# alan2.net
KiCad netlist of a schematic drawn in EAGLE
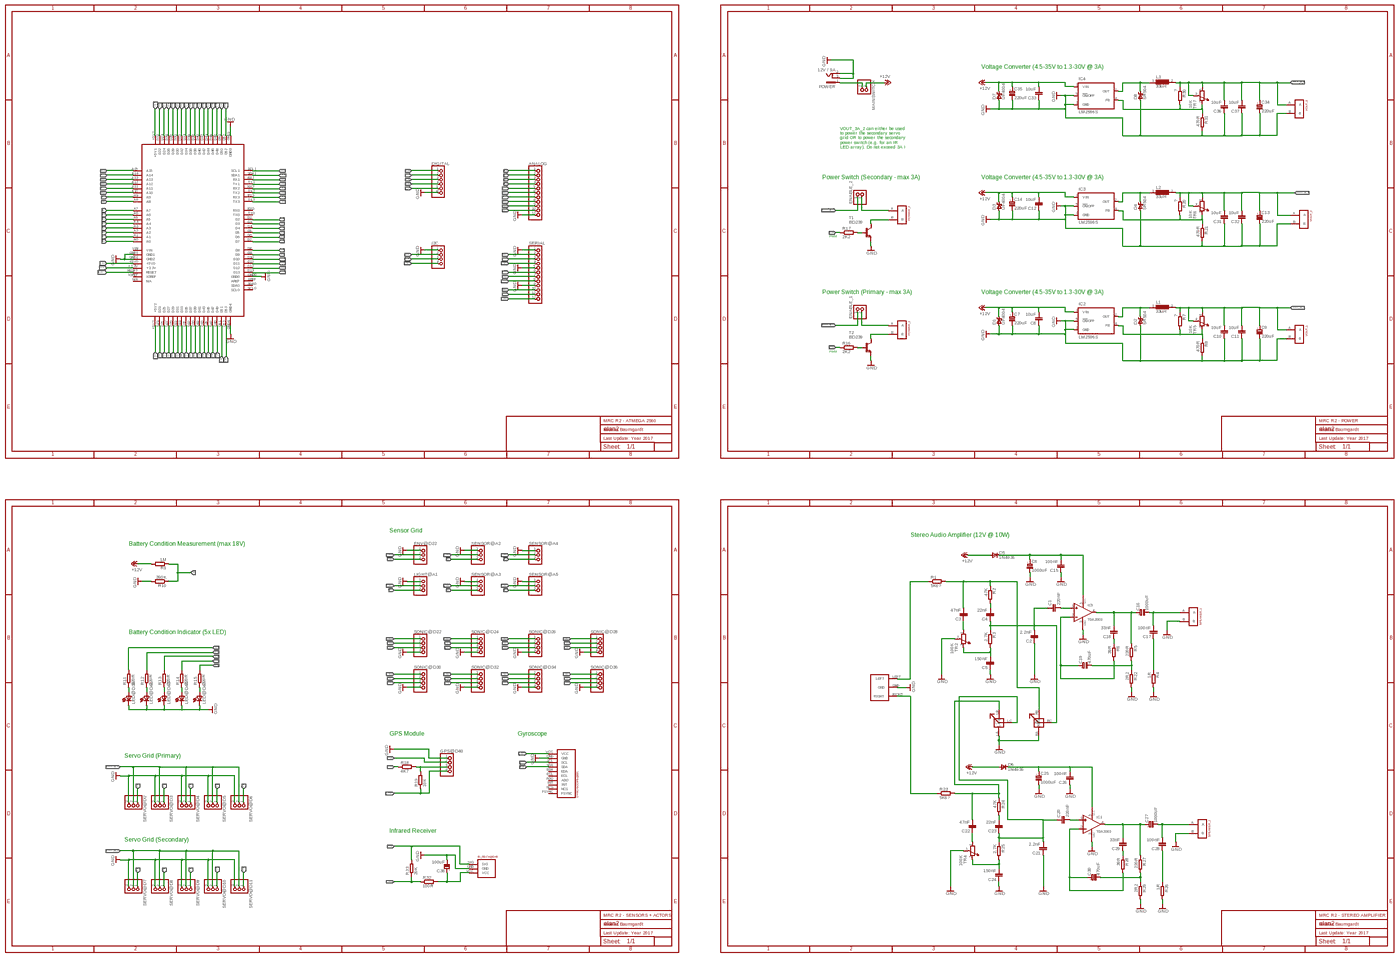
[diagram p0: schematic, sheet 1, overview]
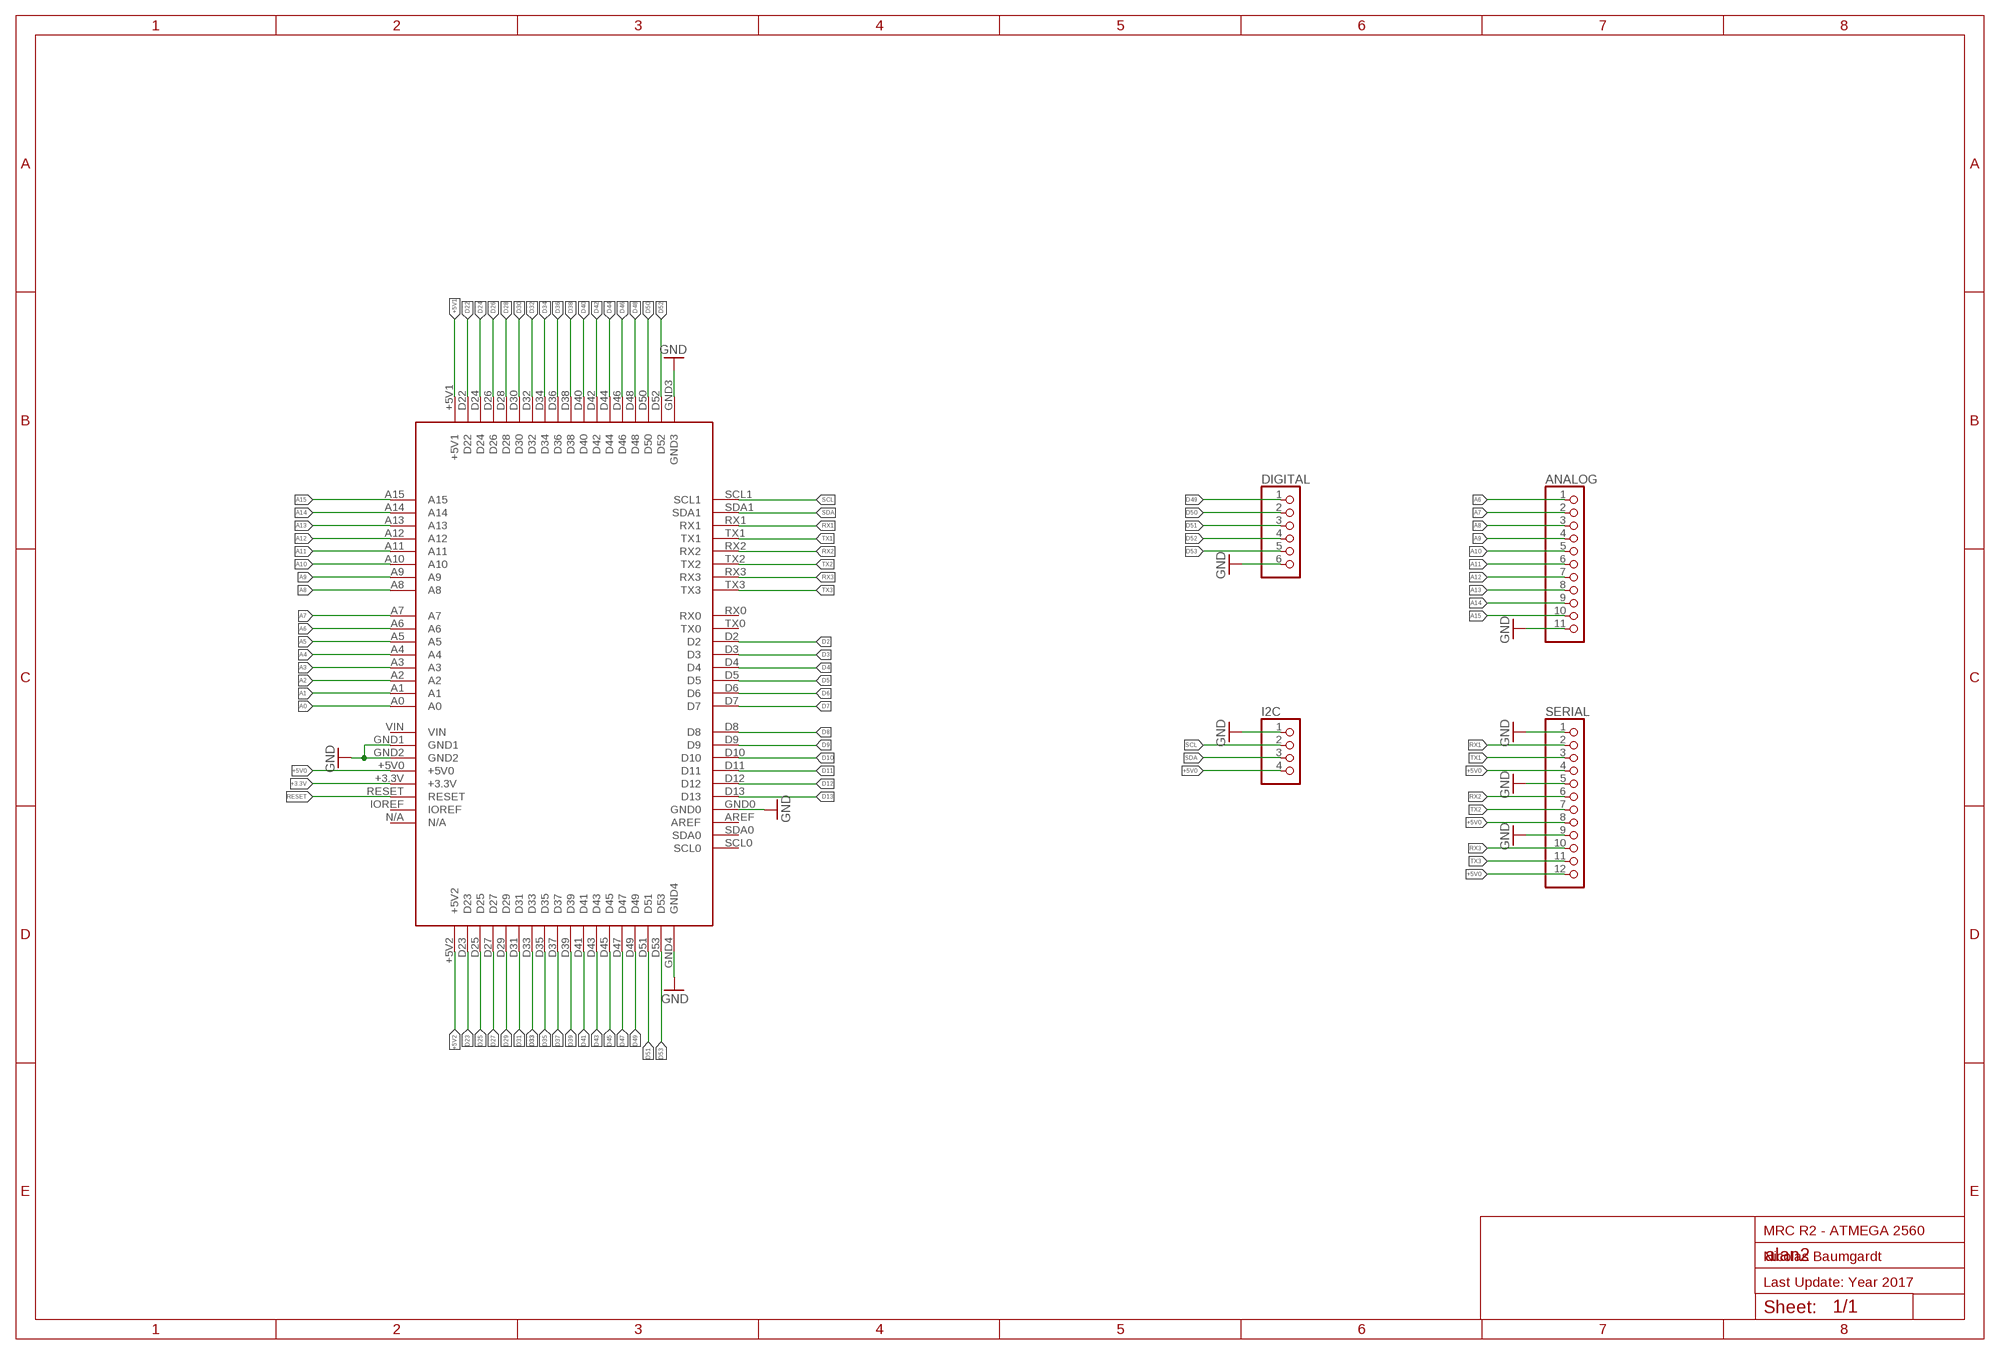
[diagram p1: schematic, sheet 1, part 1 of 4]
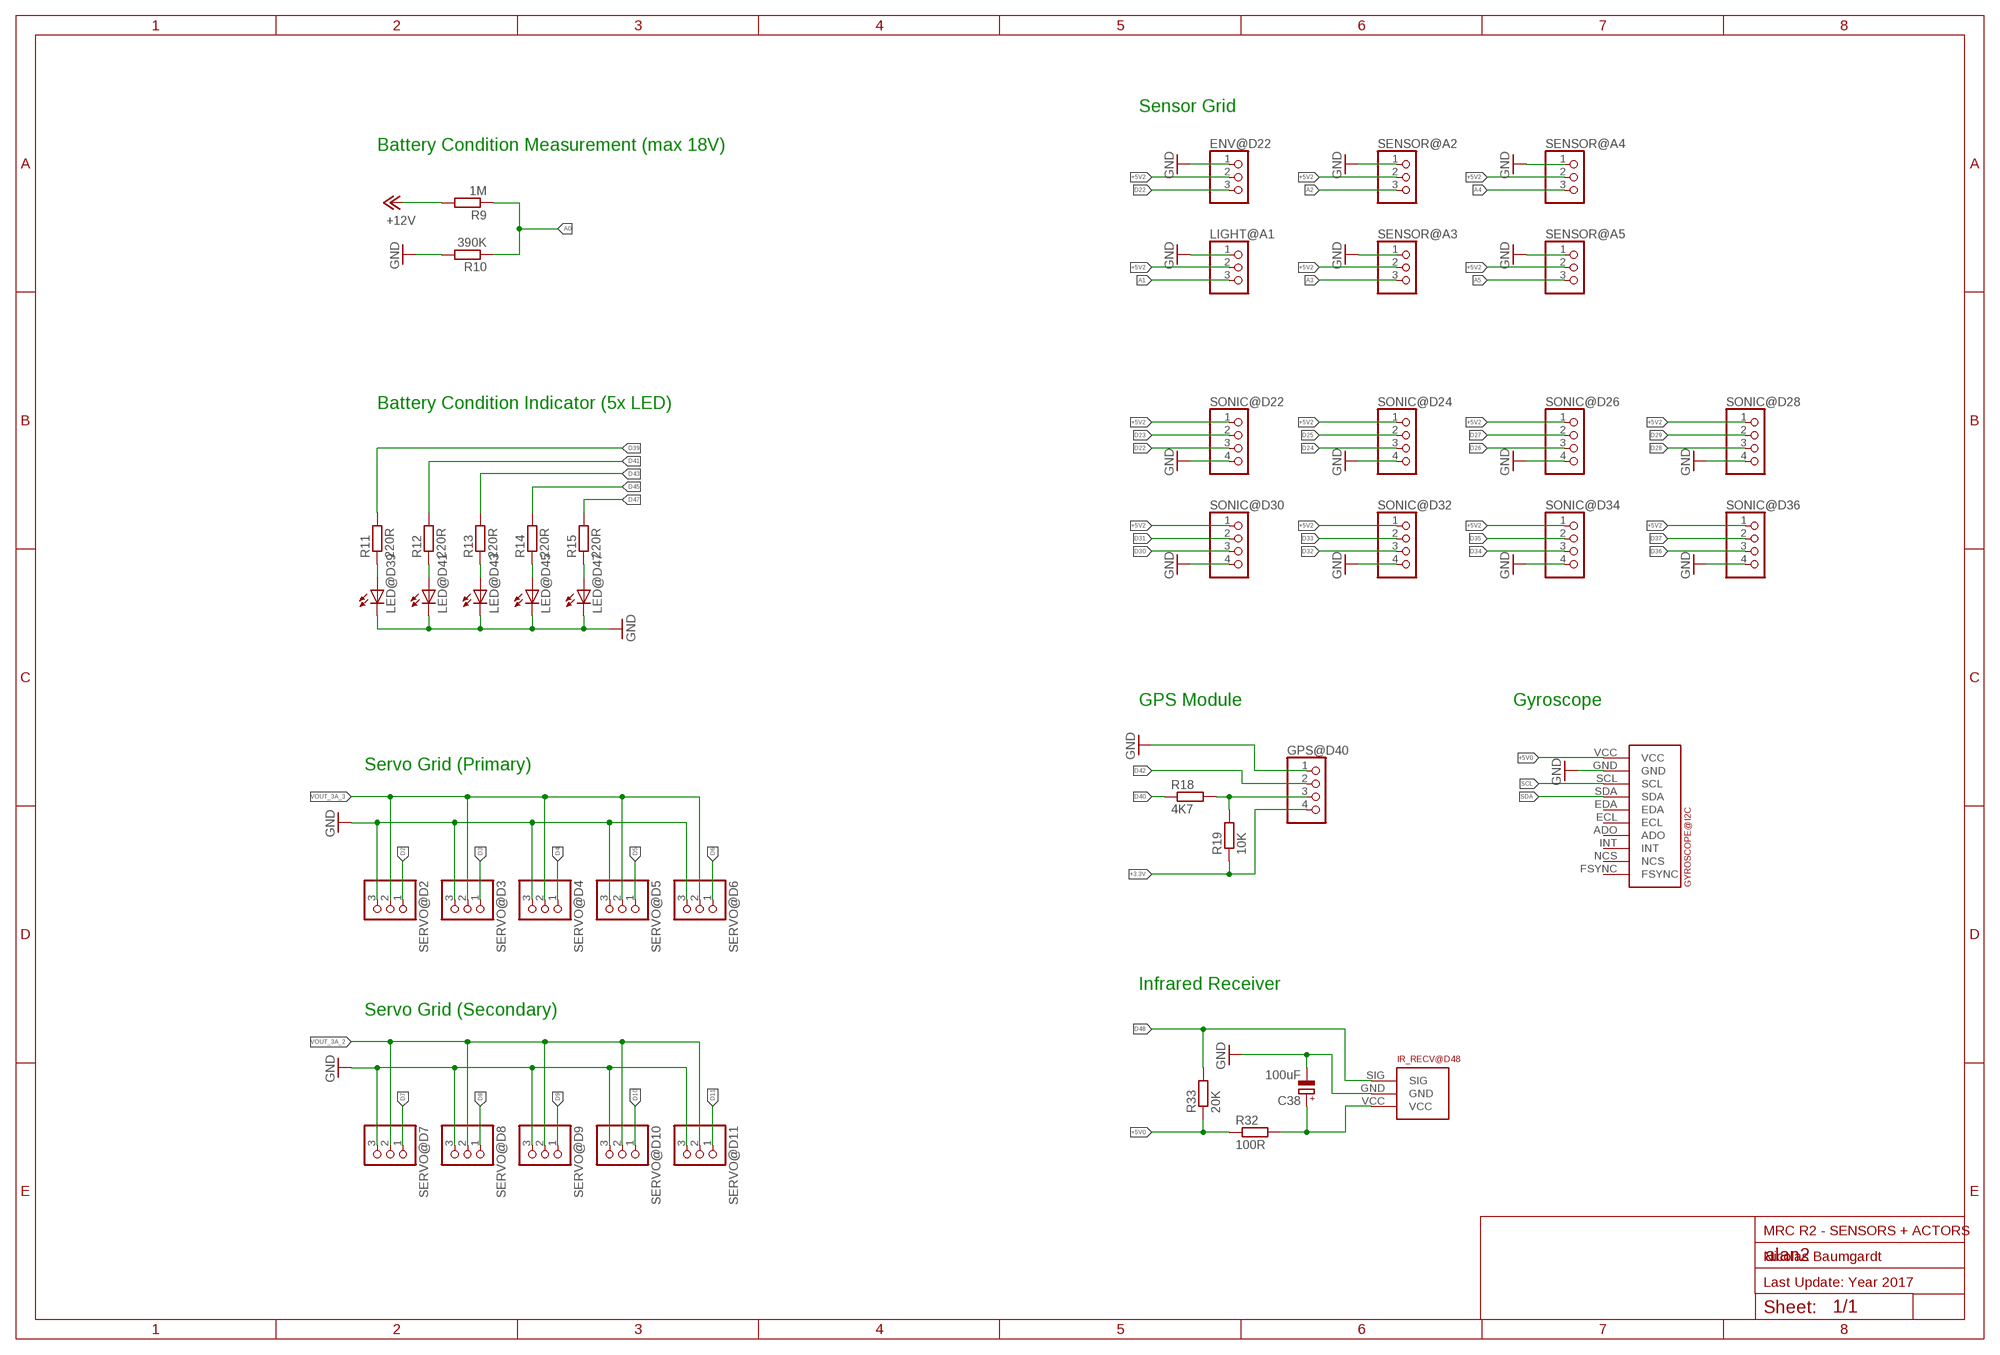
[diagram p2: schematic, sheet 1, part 2 of 4]
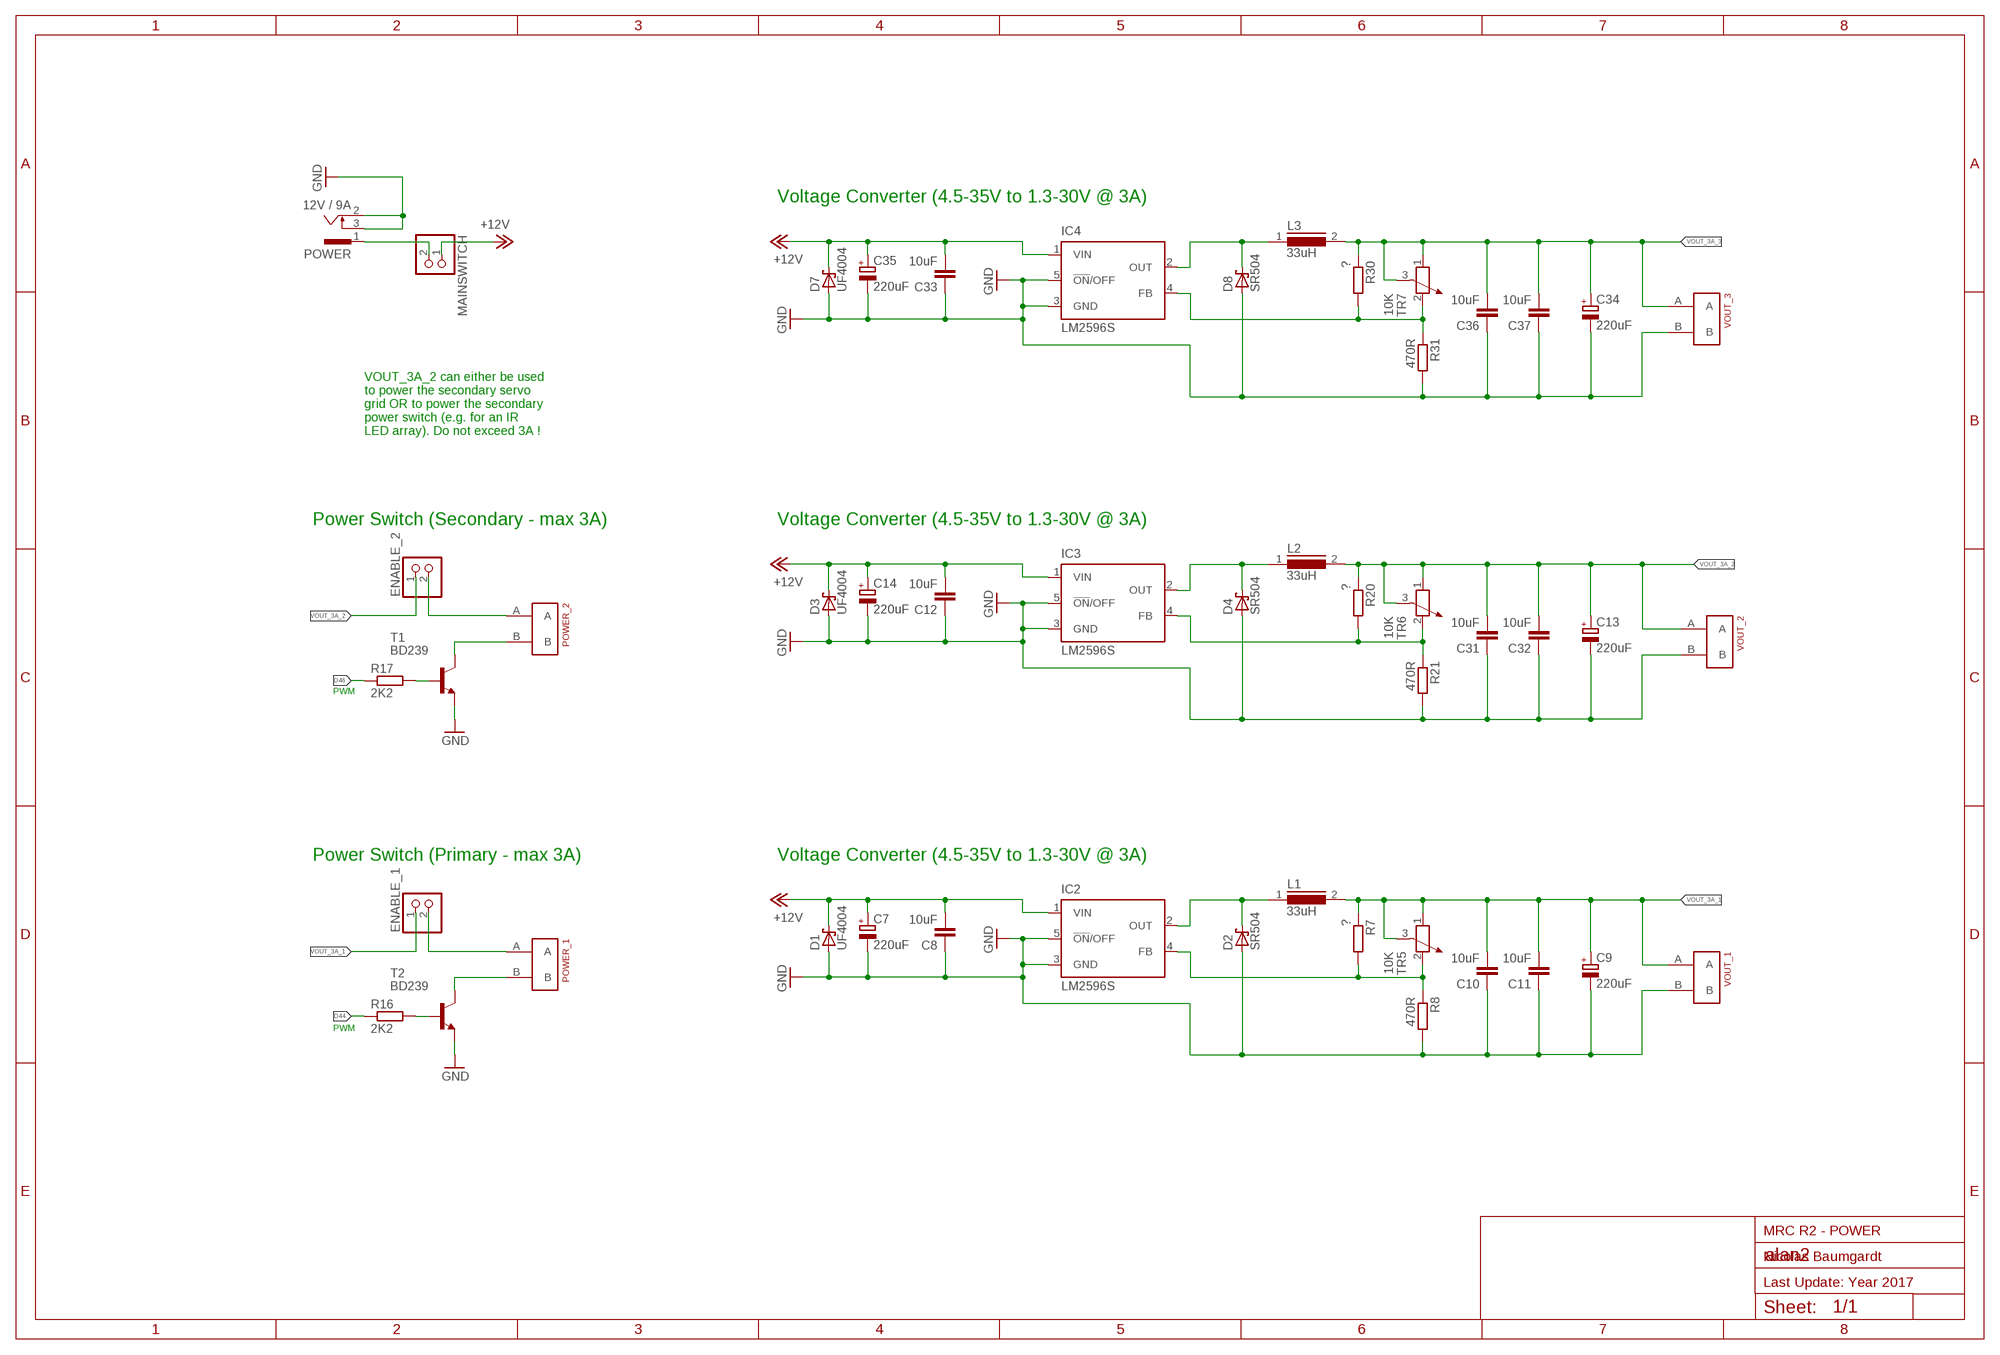
[diagram p3: schematic, sheet 1, part 3 of 4]
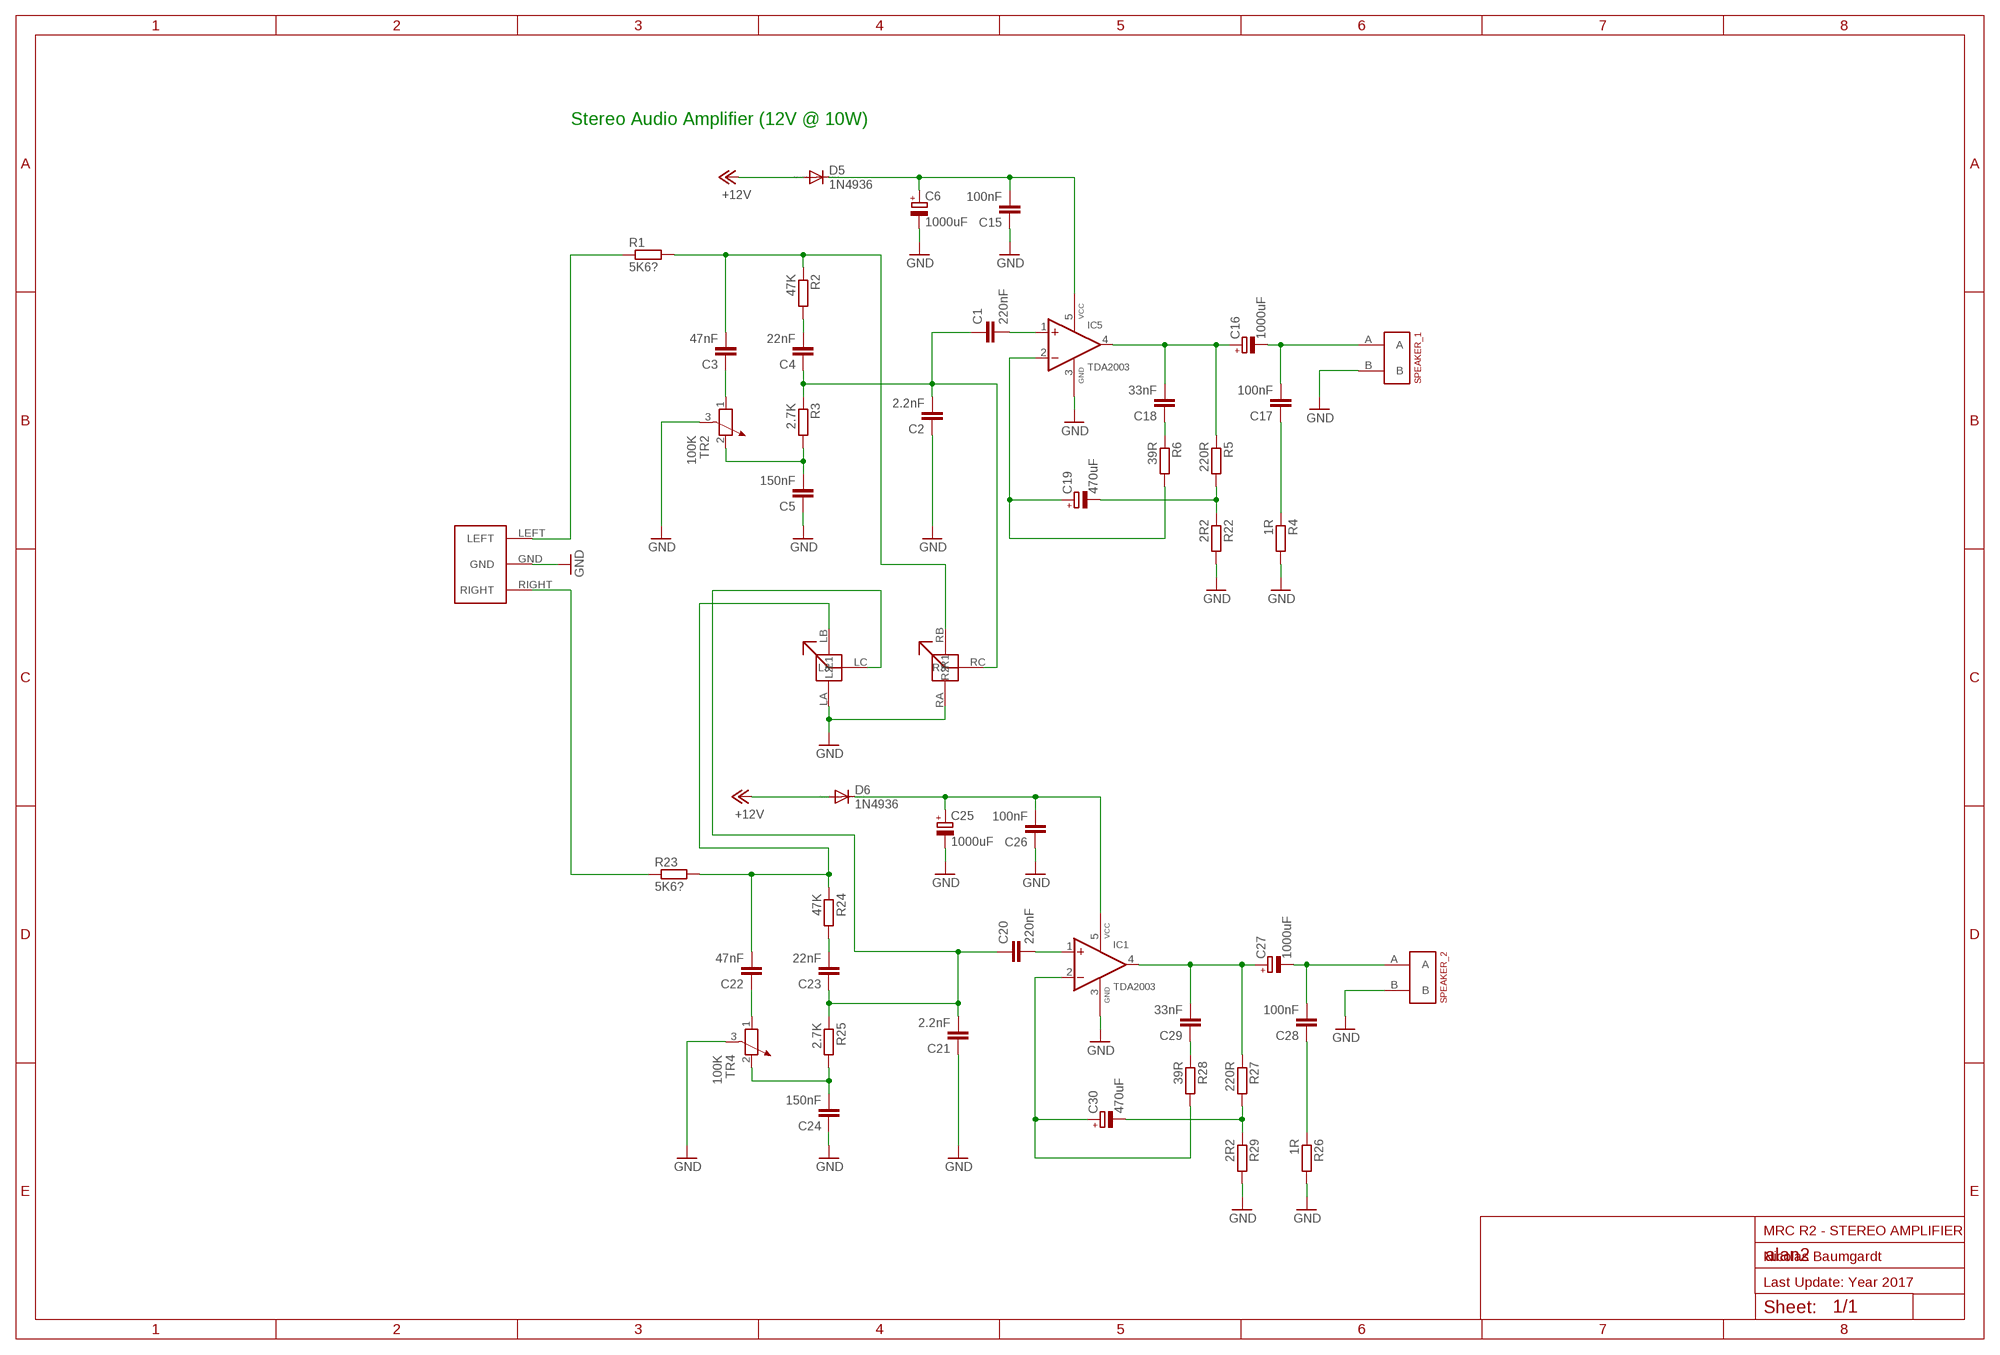
[diagram p4: schematic, sheet 1, part 4 of 4]

(export (version "E")
  (design (tool "Eeschema 10.0.6"))
  (components
    (comp (ref "ANALOG")
      (value "PINHD-1X11")
      (footprint "eagle-import:1X11")
      (libsource (lib "eagle-import") (part "PINHD-1X11"))
    )
    (comp (ref "ATMEGA")
      (value "ARDUINO_MEGA_PINOUT")
      (footprint "eagle-import:ARDUINO_MEGA_PINOUT")
      (libsource (lib "eagle-import") (part "ARDUINO_MEGA_PINOUT"))
    )
    (comp (ref "AUDIO_IN")
      (value "AUDIOJACK")
      (footprint "eagle-import:AUDIOJACK")
      (libsource (lib "eagle-import") (part "AUDIOJACK"))
    )
    (comp (ref "C1")
      (value "220nF")
      (footprint "eagle-import:C050-035X075")
      (libsource (lib "eagle-import") (part "C-EU050-035X075"))
    )
    (comp (ref "C2")
      (value "2.2nF")
      (footprint "eagle-import:C050-035X075")
      (libsource (lib "eagle-import") (part "C-EU050-035X075"))
    )
    (comp (ref "C3")
      (value "47nF")
      (footprint "eagle-import:C050-035X075")
      (libsource (lib "eagle-import") (part "C-EU050-035X075"))
    )
    (comp (ref "C4")
      (value "22nF")
      (footprint "eagle-import:C050-035X075")
      (libsource (lib "eagle-import") (part "C-EU050-035X075"))
    )
    (comp (ref "C5")
      (value "150nF")
      (footprint "eagle-import:C050-035X075")
      (libsource (lib "eagle-import") (part "C-EU050-035X075"))
    )
    (comp (ref "C6")
      (value "1000uF")
      (footprint "eagle-import:E5-13")
      (libsource (lib "eagle-import") (part "CPOL-EUE5-13"))
    )
    (comp (ref "C7")
      (value "220uF")
      (footprint "eagle-import:E5-8,5")
      (libsource (lib "eagle-import") (part "CPOL-EUE5-8.5"))
    )
    (comp (ref "C8")
      (value "10uF")
      (footprint "eagle-import:C050-035X075")
      (libsource (lib "eagle-import") (part "C-EU050-035X075"))
    )
    (comp (ref "C9")
      (value "220uF")
      (footprint "eagle-import:E5-8,5")
      (libsource (lib "eagle-import") (part "CPOL-EUE5-8.5"))
    )
    (comp (ref "C10")
      (value "10uF")
      (footprint "eagle-import:C050-035X075")
      (libsource (lib "eagle-import") (part "C-EU050-035X075"))
    )
    (comp (ref "C11")
      (value "10uF")
      (footprint "eagle-import:C050-035X075")
      (libsource (lib "eagle-import") (part "C-EU050-035X075"))
    )
    (comp (ref "C12")
      (value "10uF")
      (footprint "eagle-import:C050-035X075")
      (libsource (lib "eagle-import") (part "C-EU050-035X075"))
    )
    (comp (ref "C13")
      (value "220uF")
      (footprint "eagle-import:E5-8,5")
      (libsource (lib "eagle-import") (part "CPOL-EUE5-8.5"))
    )
    (comp (ref "C14")
      (value "220uF")
      (footprint "eagle-import:E5-8,5")
      (libsource (lib "eagle-import") (part "CPOL-EUE5-8.5"))
    )
    (comp (ref "C15")
      (value "100nF")
      (footprint "eagle-import:C050-035X075")
      (libsource (lib "eagle-import") (part "C-EU050-035X075"))
    )
    (comp (ref "C16")
      (value "1000uF")
      (footprint "eagle-import:E5-13")
      (libsource (lib "eagle-import") (part "CPOL-EUE5-13"))
    )
    (comp (ref "C17")
      (value "100nF")
      (footprint "eagle-import:C050-035X075")
      (libsource (lib "eagle-import") (part "C-EU050-035X075"))
    )
    (comp (ref "C18")
      (value "33nF")
      (footprint "eagle-import:C050-035X075")
      (libsource (lib "eagle-import") (part "C-EU050-035X075"))
    )
    (comp (ref "C19")
      (value "470uF")
      (footprint "eagle-import:E5-10,5")
      (libsource (lib "eagle-import") (part "CPOL-EUE5-10.5"))
    )
    (comp (ref "C20")
      (value "220nF")
      (footprint "eagle-import:C050-035X075")
      (libsource (lib "eagle-import") (part "C-EU050-035X075"))
    )
    (comp (ref "C21")
      (value "2.2nF")
      (footprint "eagle-import:C050-035X075")
      (libsource (lib "eagle-import") (part "C-EU050-035X075"))
    )
    (comp (ref "C22")
      (value "47nF")
      (footprint "eagle-import:C050-035X075")
      (libsource (lib "eagle-import") (part "C-EU050-035X075"))
    )
    (comp (ref "C23")
      (value "22nF")
      (footprint "eagle-import:C050-035X075")
      (libsource (lib "eagle-import") (part "C-EU050-035X075"))
    )
    (comp (ref "C24")
      (value "150nF")
      (footprint "eagle-import:C050-035X075")
      (libsource (lib "eagle-import") (part "C-EU050-035X075"))
    )
    (comp (ref "C25")
      (value "1000uF")
      (footprint "eagle-import:E5-13")
      (libsource (lib "eagle-import") (part "CPOL-EUE5-13"))
    )
    (comp (ref "C26")
      (value "100nF")
      (footprint "eagle-import:C050-035X075")
      (libsource (lib "eagle-import") (part "C-EU050-035X075"))
    )
    (comp (ref "C27")
      (value "1000uF")
      (footprint "eagle-import:E5-13")
      (libsource (lib "eagle-import") (part "CPOL-EUE5-13"))
    )
    (comp (ref "C28")
      (value "100nF")
      (footprint "eagle-import:C050-035X075")
      (libsource (lib "eagle-import") (part "C-EU050-035X075"))
    )
    (comp (ref "C29")
      (value "33nF")
      (footprint "eagle-import:C050-035X075")
      (libsource (lib "eagle-import") (part "C-EU050-035X075"))
    )
    (comp (ref "C30")
      (value "470uF")
      (footprint "eagle-import:E5-10,5")
      (libsource (lib "eagle-import") (part "CPOL-EUE5-10.5"))
    )
    (comp (ref "C31")
      (value "10uF")
      (footprint "eagle-import:C050-035X075")
      (libsource (lib "eagle-import") (part "C-EU050-035X075"))
    )
    (comp (ref "C32")
      (value "10uF")
      (footprint "eagle-import:C050-035X075")
      (libsource (lib "eagle-import") (part "C-EU050-035X075"))
    )
    (comp (ref "C33")
      (value "10uF")
      (footprint "eagle-import:C050-035X075")
      (libsource (lib "eagle-import") (part "C-EU050-035X075"))
    )
    (comp (ref "C34")
      (value "220uF")
      (footprint "eagle-import:E5-8,5")
      (libsource (lib "eagle-import") (part "CPOL-EUE5-8.5"))
    )
    (comp (ref "C35")
      (value "220uF")
      (footprint "eagle-import:E5-8,5")
      (libsource (lib "eagle-import") (part "CPOL-EUE5-8.5"))
    )
    (comp (ref "C36")
      (value "10uF")
      (footprint "eagle-import:C050-035X075")
      (libsource (lib "eagle-import") (part "C-EU050-035X075"))
    )
    (comp (ref "C37")
      (value "10uF")
      (footprint "eagle-import:C050-035X075")
      (libsource (lib "eagle-import") (part "C-EU050-035X075"))
    )
    (comp (ref "C38")
      (value "100uF")
      (footprint "eagle-import:E2,5-5")
      (libsource (lib "eagle-import") (part "CPOL-EUE2.5-5"))
    )
    (comp (ref "D1")
      (value "UF4004")
      (footprint "eagle-import:DO41-7.6")
      (libsource (lib "eagle-import") (part "1N5817-T"))
    )
    (comp (ref "D2")
      (value "SR504")
      (footprint "eagle-import:DO41-7.6")
      (libsource (lib "eagle-import") (part "1N5817-T"))
    )
    (comp (ref "D3")
      (value "UF4004")
      (footprint "eagle-import:DO41-7.6")
      (libsource (lib "eagle-import") (part "1N5817-T"))
    )
    (comp (ref "D4")
      (value "SR504")
      (footprint "eagle-import:DO41-7.6")
      (libsource (lib "eagle-import") (part "1N5817-T"))
    )
    (comp (ref "D5")
      (value "1N4936")
      (footprint "eagle-import:DO41-10")
      (libsource (lib "eagle-import") (part "1N4004"))
    )
    (comp (ref "D6")
      (value "1N4936")
      (footprint "eagle-import:DO41-10")
      (libsource (lib "eagle-import") (part "1N4004"))
    )
    (comp (ref "D7")
      (value "UF4004")
      (footprint "eagle-import:DO41-7.6")
      (libsource (lib "eagle-import") (part "1N5817-T"))
    )
    (comp (ref "D8")
      (value "SR504")
      (footprint "eagle-import:DO41-7.6")
      (libsource (lib "eagle-import") (part "1N5817-T"))
    )
    (comp (ref "DIGITAL")
      (value "PINHD-1X6")
      (footprint "eagle-import:1X06")
      (libsource (lib "eagle-import") (part "PINHD-1X6"))
    )
    (comp (ref "ENABLE_1")
      (value "PINHD-1X2")
      (footprint "eagle-import:1X02")
      (libsource (lib "eagle-import") (part "PINHD-1X2"))
    )
    (comp (ref "ENABLE_2")
      (value "PINHD-1X2")
      (footprint "eagle-import:1X02")
      (libsource (lib "eagle-import") (part "PINHD-1X2"))
    )
    (comp (ref "ENV@D22")
      (value "PINHD-1X3")
      (footprint "eagle-import:1X03")
      (libsource (lib "eagle-import") (part "PINHD-1X3"))
    )
    (comp (ref "GPS@D40")
      (value "PINHD-1X4")
      (footprint "eagle-import:1X04")
      (libsource (lib "eagle-import") (part "PINHD-1X4"))
    )
    (comp (ref "GYROSCOPE@I2C")
      (value "GYROSCOPE")
      (footprint "eagle-import:GYROSCOPE")
      (libsource (lib "eagle-import") (part "GYROSCOPE"))
    )
    (comp (ref "I2C")
      (value "PINHD-1X4")
      (footprint "eagle-import:1X04")
      (libsource (lib "eagle-import") (part "PINHD-1X4"))
    )
    (comp (ref "IC1")
      (value "TDA2003")
      (footprint "eagle-import:PENTAWATT-V")
      (libsource (lib "eagle-import") (part "TDA2003"))
    )
    (comp (ref "IC2")
      (value "LM2596S")
      (footprint "eagle-import:TO263-5")
      (fields (field (name "MF") "NATIONAL SEMICONDUCTOR") (field (name "MPN") "LM2596S-ADJ/NOPB"))
      (libsource (lib "eagle-import") (part "LM2596S"))
    )
    (comp (ref "IC3")
      (value "LM2596S")
      (footprint "eagle-import:TO263-5")
      (fields (field (name "MF") "NATIONAL SEMICONDUCTOR") (field (name "MPN") "LM2596S-ADJ/NOPB"))
      (libsource (lib "eagle-import") (part "LM2596S"))
    )
    (comp (ref "IC4")
      (value "LM2596S")
      (footprint "eagle-import:TO263-5")
      (fields (field (name "MF") "NATIONAL SEMICONDUCTOR") (field (name "MPN") "LM2596S-ADJ/NOPB"))
      (libsource (lib "eagle-import") (part "LM2596S"))
    )
    (comp (ref "IC5")
      (value "TDA2003")
      (footprint "eagle-import:PENTAWATT-V")
      (libsource (lib "eagle-import") (part "TDA2003"))
    )
    (comp (ref "IR_RECV@D48")
      (value "TSOP1838")
      (footprint "eagle-import:TSOP1838")
      (libsource (lib "eagle-import") (part "TSOP1838"))
    )
    (comp (ref "L1")
      (value "33uH")
      (footprint "eagle-import:SFT830D")
      (libsource (lib "eagle-import") (part "SFT830D"))
    )
    (comp (ref "L2")
      (value "33uH")
      (footprint "eagle-import:SFT830D")
      (libsource (lib "eagle-import") (part "SFT830D"))
    )
    (comp (ref "L3")
      (value "33uH")
      (footprint "eagle-import:SFT830D")
      (libsource (lib "eagle-import") (part "SFT830D"))
    )
    (comp (ref "LED@D39")
      (value "LED5MM")
      (footprint "eagle-import:LED5MM")
      (libsource (lib "eagle-import") (part "LED5MM"))
    )
    (comp (ref "LED@D41")
      (value "LED5MM")
      (footprint "eagle-import:LED5MM")
      (libsource (lib "eagle-import") (part "LED5MM"))
    )
    (comp (ref "LED@D43")
      (value "LED5MM")
      (footprint "eagle-import:LED5MM")
      (libsource (lib "eagle-import") (part "LED5MM"))
    )
    (comp (ref "LED@D45")
      (value "LED5MM")
      (footprint "eagle-import:LED5MM")
      (libsource (lib "eagle-import") (part "LED5MM"))
    )
    (comp (ref "LED@D47")
      (value "LED5MM")
      (footprint "eagle-import:LED5MM")
      (libsource (lib "eagle-import") (part "LED5MM"))
    )
    (comp (ref "LIGHT@A1")
      (value "PINHD-1X3")
      (footprint "eagle-import:1X03")
      (libsource (lib "eagle-import") (part "PINHD-1X3"))
    )
    (comp (ref "MAINSWITCH")
      (value "PINHD-1X2")
      (footprint "eagle-import:1X02")
      (libsource (lib "eagle-import") (part "PINHD-1X2"))
    )
    (comp (ref "POWER")
      (value "12V / 9A")
      (footprint "eagle-import:SCD-014-A")
      (libsource (lib "eagle-import") (part "SCD-014A"))
    )
    (comp (ref "POWER_1")
      (value "TERMINAL_BLOCK")
      (footprint "eagle-import:TERMINAL_BLOCK")
      (libsource (lib "eagle-import") (part "TERMINAL_BLOCK"))
    )
    (comp (ref "POWER_2")
      (value "TERMINAL_BLOCK")
      (footprint "eagle-import:TERMINAL_BLOCK")
      (libsource (lib "eagle-import") (part "TERMINAL_BLOCK"))
    )
    (comp (ref "R1")
      (value "5K6?")
      (footprint "eagle-import:0204_7")
      (libsource (lib "eagle-import") (part "R-EU_0204/7"))
    )
    (comp (ref "R2")
      (value "47K")
      (footprint "eagle-import:0204_7")
      (libsource (lib "eagle-import") (part "R-EU_0204/7"))
    )
    (comp (ref "R3")
      (value "2.7K")
      (footprint "eagle-import:0204_7")
      (libsource (lib "eagle-import") (part "R-EU_0204/7"))
    )
    (comp (ref "R4")
      (value "1R")
      (footprint "eagle-import:0204_7")
      (libsource (lib "eagle-import") (part "R-EU_0204/7"))
    )
    (comp (ref "R5")
      (value "220R")
      (footprint "eagle-import:0204_7")
      (libsource (lib "eagle-import") (part "R-EU_0204/7"))
    )
    (comp (ref "R6")
      (value "39R")
      (footprint "eagle-import:0204_7")
      (libsource (lib "eagle-import") (part "R-EU_0204/7"))
    )
    (comp (ref "R7")
      (value "?")
      (footprint "eagle-import:0204_7")
      (libsource (lib "eagle-import") (part "R-EU_0204/7"))
    )
    (comp (ref "R8")
      (value "470R")
      (footprint "eagle-import:0204_7")
      (libsource (lib "eagle-import") (part "R-EU_0204/7"))
    )
    (comp (ref "R9")
      (value "1M")
      (footprint "eagle-import:0207_7")
      (libsource (lib "eagle-import") (part "R-EU_0207/7"))
    )
    (comp (ref "R10")
      (value "390K")
      (footprint "eagle-import:0207_7")
      (libsource (lib "eagle-import") (part "R-EU_0207/7"))
    )
    (comp (ref "R11")
      (value "220R")
      (footprint "eagle-import:0204_7")
      (libsource (lib "eagle-import") (part "R-EU_0204/7"))
    )
    (comp (ref "R12")
      (value "220R")
      (footprint "eagle-import:0204_7")
      (libsource (lib "eagle-import") (part "R-EU_0204/7"))
    )
    (comp (ref "R13")
      (value "220R")
      (footprint "eagle-import:0204_7")
      (libsource (lib "eagle-import") (part "R-EU_0204/7"))
    )
    (comp (ref "R14")
      (value "220R")
      (footprint "eagle-import:0204_7")
      (libsource (lib "eagle-import") (part "R-EU_0204/7"))
    )
    (comp (ref "R15")
      (value "220R")
      (footprint "eagle-import:0204_7")
      (libsource (lib "eagle-import") (part "R-EU_0204/7"))
    )
    (comp (ref "R16")
      (value "2K2")
      (footprint "eagle-import:0207_7")
      (libsource (lib "eagle-import") (part "R-EU_0207/7"))
    )
    (comp (ref "R17")
      (value "2K2")
      (footprint "eagle-import:0207_7")
      (libsource (lib "eagle-import") (part "R-EU_0207/7"))
    )
    (comp (ref "R18")
      (value "4K7")
      (footprint "eagle-import:0204_7")
      (libsource (lib "eagle-import") (part "R-EU_0204/7"))
    )
    (comp (ref "R19")
      (value "10K")
      (footprint "eagle-import:0204_7")
      (libsource (lib "eagle-import") (part "R-EU_0204/7"))
    )
    (comp (ref "R20")
      (value "?")
      (footprint "eagle-import:0204_7")
      (libsource (lib "eagle-import") (part "R-EU_0204/7"))
    )
    (comp (ref "R21")
      (value "470R")
      (footprint "eagle-import:0204_7")
      (libsource (lib "eagle-import") (part "R-EU_0204/7"))
    )
    (comp (ref "R22")
      (value "2R2")
      (footprint "eagle-import:0204_7")
      (libsource (lib "eagle-import") (part "R-EU_0204/7"))
    )
    (comp (ref "R23")
      (value "5K6?")
      (footprint "eagle-import:0204_7")
      (libsource (lib "eagle-import") (part "R-EU_0204/7"))
    )
    (comp (ref "R24")
      (value "47K")
      (footprint "eagle-import:0204_7")
      (libsource (lib "eagle-import") (part "R-EU_0204/7"))
    )
    (comp (ref "R25")
      (value "2.7K")
      (footprint "eagle-import:0204_7")
      (libsource (lib "eagle-import") (part "R-EU_0204/7"))
    )
    (comp (ref "R26")
      (value "1R")
      (footprint "eagle-import:0204_7")
      (libsource (lib "eagle-import") (part "R-EU_0204/7"))
    )
    (comp (ref "R27")
      (value "220R")
      (footprint "eagle-import:0204_7")
      (libsource (lib "eagle-import") (part "R-EU_0204/7"))
    )
    (comp (ref "R28")
      (value "39R")
      (footprint "eagle-import:0204_7")
      (libsource (lib "eagle-import") (part "R-EU_0204/7"))
    )
    (comp (ref "R29")
      (value "2R2")
      (footprint "eagle-import:0204_7")
      (libsource (lib "eagle-import") (part "R-EU_0204/7"))
    )
    (comp (ref "R30")
      (value "?")
      (footprint "eagle-import:0204_7")
      (libsource (lib "eagle-import") (part "R-EU_0204/7"))
    )
    (comp (ref "R31")
      (value "470R")
      (footprint "eagle-import:0204_7")
      (libsource (lib "eagle-import") (part "R-EU_0204/7"))
    )
    (comp (ref "R32")
      (value "100R")
      (footprint "eagle-import:0204_7")
      (libsource (lib "eagle-import") (part "R-EU_0204/7"))
    )
    (comp (ref "R33")
      (value "20K")
      (footprint "eagle-import:0204_7")
      (libsource (lib "eagle-import") (part "R-EU_0204/7"))
    )
    (comp (ref "SENSOR@A2")
      (value "PINHD-1X3")
      (footprint "eagle-import:1X03")
      (libsource (lib "eagle-import") (part "PINHD-1X3"))
    )
    (comp (ref "SENSOR@A3")
      (value "PINHD-1X3")
      (footprint "eagle-import:1X03")
      (libsource (lib "eagle-import") (part "PINHD-1X3"))
    )
    (comp (ref "SENSOR@A4")
      (value "PINHD-1X3")
      (footprint "eagle-import:1X03")
      (libsource (lib "eagle-import") (part "PINHD-1X3"))
    )
    (comp (ref "SENSOR@A5")
      (value "PINHD-1X3")
      (footprint "eagle-import:1X03")
      (libsource (lib "eagle-import") (part "PINHD-1X3"))
    )
    (comp (ref "SERIAL")
      (value "PINHD-1X12")
      (footprint "eagle-import:1X12")
      (libsource (lib "eagle-import") (part "PINHD-1X12"))
    )
    (comp (ref "SERVO@D2")
      (value "PINHD-1X3")
      (footprint "eagle-import:1X03")
      (libsource (lib "eagle-import") (part "PINHD-1X3"))
    )
    (comp (ref "SERVO@D3")
      (value "PINHD-1X3")
      (footprint "eagle-import:1X03")
      (libsource (lib "eagle-import") (part "PINHD-1X3"))
    )
    (comp (ref "SERVO@D4")
      (value "PINHD-1X3")
      (footprint "eagle-import:1X03")
      (libsource (lib "eagle-import") (part "PINHD-1X3"))
    )
    (comp (ref "SERVO@D5")
      (value "PINHD-1X3")
      (footprint "eagle-import:1X03")
      (libsource (lib "eagle-import") (part "PINHD-1X3"))
    )
    (comp (ref "SERVO@D6")
      (value "PINHD-1X3")
      (footprint "eagle-import:1X03")
      (libsource (lib "eagle-import") (part "PINHD-1X3"))
    )
    (comp (ref "SERVO@D7")
      (value "PINHD-1X3")
      (footprint "eagle-import:1X03")
      (libsource (lib "eagle-import") (part "PINHD-1X3"))
    )
    (comp (ref "SERVO@D8")
      (value "PINHD-1X3")
      (footprint "eagle-import:1X03")
      (libsource (lib "eagle-import") (part "PINHD-1X3"))
    )
    (comp (ref "SERVO@D9")
      (value "PINHD-1X3")
      (footprint "eagle-import:1X03")
      (libsource (lib "eagle-import") (part "PINHD-1X3"))
    )
    (comp (ref "SERVO@D10")
      (value "PINHD-1X3")
      (footprint "eagle-import:1X03")
      (libsource (lib "eagle-import") (part "PINHD-1X3"))
    )
    (comp (ref "SERVO@D11")
      (value "PINHD-1X3")
      (footprint "eagle-import:1X03")
      (libsource (lib "eagle-import") (part "PINHD-1X3"))
    )
    (comp (ref "SONIC@D22")
      (value "PINHD-1X4")
      (footprint "eagle-import:1X04")
      (libsource (lib "eagle-import") (part "PINHD-1X4"))
    )
    (comp (ref "SONIC@D24")
      (value "PINHD-1X4")
      (footprint "eagle-import:1X04")
      (libsource (lib "eagle-import") (part "PINHD-1X4"))
    )
    (comp (ref "SONIC@D26")
      (value "PINHD-1X4")
      (footprint "eagle-import:1X04")
      (libsource (lib "eagle-import") (part "PINHD-1X4"))
    )
    (comp (ref "SONIC@D28")
      (value "PINHD-1X4")
      (footprint "eagle-import:1X04")
      (libsource (lib "eagle-import") (part "PINHD-1X4"))
    )
    (comp (ref "SONIC@D30")
      (value "PINHD-1X4")
      (footprint "eagle-import:1X04")
      (libsource (lib "eagle-import") (part "PINHD-1X4"))
    )
    (comp (ref "SONIC@D32")
      (value "PINHD-1X4")
      (footprint "eagle-import:1X04")
      (libsource (lib "eagle-import") (part "PINHD-1X4"))
    )
    (comp (ref "SONIC@D34")
      (value "PINHD-1X4")
      (footprint "eagle-import:1X04")
      (libsource (lib "eagle-import") (part "PINHD-1X4"))
    )
    (comp (ref "SONIC@D36")
      (value "PINHD-1X4")
      (footprint "eagle-import:1X04")
      (libsource (lib "eagle-import") (part "PINHD-1X4"))
    )
    (comp (ref "SPEAKER_1")
      (value "TERMINAL_BLOCK")
      (footprint "eagle-import:TERMINAL_BLOCK")
      (libsource (lib "eagle-import") (part "TERMINAL_BLOCK"))
    )
    (comp (ref "SPEAKER_2")
      (value "TERMINAL_BLOCK")
      (footprint "eagle-import:TERMINAL_BLOCK")
      (libsource (lib "eagle-import") (part "TERMINAL_BLOCK"))
    )
    (comp (ref "T1")
      (value "BD239")
      (footprint "eagle-import:TO220")
      (libsource (lib "eagle-import") (part "BD239"))
    )
    (comp (ref "T2")
      (value "BD239")
      (footprint "eagle-import:TO220")
      (libsource (lib "eagle-import") (part "BD239"))
    )
    (comp (ref "TR2")
      (value "100K")
      (footprint "eagle-import:PT-10")
      (libsource (lib "eagle-import") (part "POTENTIOMETER_PT-10"))
    )
    (comp (ref "TR4")
      (value "100K")
      (footprint "eagle-import:PT-10")
      (libsource (lib "eagle-import") (part "POTENTIOMETER_PT-10"))
    )
    (comp (ref "TR5")
      (value "10K")
      (footprint "eagle-import:PT-10")
      (libsource (lib "eagle-import") (part "POTENTIOMETER_PT-10"))
    )
    (comp (ref "TR6")
      (value "10K")
      (footprint "eagle-import:PT-10")
      (libsource (lib "eagle-import") (part "POTENTIOMETER_PT-10"))
    )
    (comp (ref "TR7")
      (value "10K")
      (footprint "eagle-import:PT-10")
      (libsource (lib "eagle-import") (part "POTENTIOMETER_PT-10"))
    )
    (comp (ref "U$2")
      (value "POTI_STEREO")
      (footprint "eagle-import:POTI_STEREO")
      (libsource (lib "eagle-import") (part "POTI_STEREO"))
    )
    (comp (ref "VOUT_1")
      (value "TERMINAL_BLOCK")
      (footprint "eagle-import:TERMINAL_BLOCK")
      (libsource (lib "eagle-import") (part "TERMINAL_BLOCK"))
    )
    (comp (ref "VOUT_2")
      (value "TERMINAL_BLOCK")
      (footprint "eagle-import:TERMINAL_BLOCK")
      (libsource (lib "eagle-import") (part "TERMINAL_BLOCK"))
    )
    (comp (ref "VOUT_3")
      (value "TERMINAL_BLOCK")
      (footprint "eagle-import:TERMINAL_BLOCK")
      (libsource (lib "eagle-import") (part "TERMINAL_BLOCK"))
    )
  )
  (nets
    (net (code "1") (name "+3.3V") (class "Default")
      (node (ref "ATMEGA") (pin "+3.3V") (pinfunction "+3.3V_+3.3V") (pintype "bidirectional"))
      (node (ref "GPS@D40") (pin "4") (pinfunction "4_4") (pintype "passive"))
      (node (ref "R19") (pin "1") (pinfunction "1_1") (pintype "passive"))
    )
    (net (code "2") (name "+5V0") (class "Default")
      (node (ref "ATMEGA") (pin "+5V0") (pinfunction "+5V0_+5V0") (pintype "bidirectional"))
      (node (ref "GYROSCOPE@I2C") (pin "VCC") (pinfunction "VCC_VCC") (pintype "bidirectional"))
      (node (ref "I2C") (pin "4") (pinfunction "4_4") (pintype "passive"))
      (node (ref "R32") (pin "1") (pinfunction "1_1") (pintype "passive"))
      (node (ref "R33") (pin "1") (pinfunction "1_1") (pintype "passive"))
      (node (ref "SERIAL") (pin "12") (pinfunction "12_12") (pintype "passive"))
      (node (ref "SERIAL") (pin "4") (pinfunction "4_4") (pintype "passive"))
      (node (ref "SERIAL") (pin "8") (pinfunction "8_8") (pintype "passive"))
    )
    (net (code "3") (name "+5V1") (class "Default")
      (node (ref "ATMEGA") (pin "+5V1") (pinfunction "+5V1_+5V1") (pintype "bidirectional"))
    )
    (net (code "4") (name "+5V2") (class "Default")
      (node (ref "ATMEGA") (pin "+5V2") (pinfunction "+5V2_+5V2") (pintype "bidirectional"))
      (node (ref "ENV@D22") (pin "2") (pinfunction "2_2") (pintype "passive"))
      (node (ref "LIGHT@A1") (pin "2") (pinfunction "2_2") (pintype "passive"))
      (node (ref "SENSOR@A2") (pin "2") (pinfunction "2_2") (pintype "passive"))
      (node (ref "SENSOR@A3") (pin "2") (pinfunction "2_2") (pintype "passive"))
      (node (ref "SENSOR@A4") (pin "2") (pinfunction "2_2") (pintype "passive"))
      (node (ref "SENSOR@A5") (pin "2") (pinfunction "2_2") (pintype "passive"))
      (node (ref "SONIC@D22") (pin "1") (pinfunction "1_1") (pintype "passive"))
      (node (ref "SONIC@D24") (pin "1") (pinfunction "1_1") (pintype "passive"))
      (node (ref "SONIC@D26") (pin "1") (pinfunction "1_1") (pintype "passive"))
      (node (ref "SONIC@D28") (pin "1") (pinfunction "1_1") (pintype "passive"))
      (node (ref "SONIC@D30") (pin "1") (pinfunction "1_1") (pintype "passive"))
      (node (ref "SONIC@D32") (pin "1") (pinfunction "1_1") (pintype "passive"))
      (node (ref "SONIC@D34") (pin "1") (pinfunction "1_1") (pintype "passive"))
      (node (ref "SONIC@D36") (pin "1") (pinfunction "1_1") (pintype "passive"))
    )
    (net (code "5") (name "+12V") (class "Default")
      (node (ref "C12") (pin "2") (pinfunction "2_2") (pintype "passive"))
      (node (ref "C14") (pin "+") (pinfunction "+_+") (pintype "passive"))
      (node (ref "C33") (pin "2") (pinfunction "2_2") (pintype "passive"))
      (node (ref "C35") (pin "+") (pinfunction "+_+") (pintype "passive"))
      (node (ref "C7") (pin "+") (pinfunction "+_+") (pintype "passive"))
      (node (ref "C8") (pin "2") (pinfunction "2_2") (pintype "passive"))
      (node (ref "D1") (pin "C") (pinfunction "C_C") (pintype "passive"))
      (node (ref "D3") (pin "C") (pinfunction "C_C") (pintype "passive"))
      (node (ref "D5") (pin "A") (pinfunction "A_A") (pintype "passive"))
      (node (ref "D6") (pin "A") (pinfunction "A_A") (pintype "passive"))
      (node (ref "D7") (pin "C") (pinfunction "C_C") (pintype "passive"))
      (node (ref "IC2") (pin "1") (pinfunction "VIN_1") (pintype "input"))
      (node (ref "IC3") (pin "1") (pinfunction "VIN_1") (pintype "input"))
      (node (ref "IC4") (pin "1") (pinfunction "VIN_1") (pintype "input"))
      (node (ref "MAINSWITCH") (pin "1") (pinfunction "1_1") (pintype "passive"))
      (node (ref "R9") (pin "2") (pinfunction "2_2") (pintype "passive"))
    )
    (net (code "6") (name "A0") (class "Default")
      (node (ref "ATMEGA") (pin "A0") (pinfunction "A0_A0") (pintype "bidirectional"))
      (node (ref "R10") (pin "1") (pinfunction "1_1") (pintype "passive"))
      (node (ref "R9") (pin "1") (pinfunction "1_1") (pintype "passive"))
    )
    (net (code "7") (name "A1") (class "Default")
      (node (ref "ATMEGA") (pin "A1") (pinfunction "A1_A1") (pintype "bidirectional"))
      (node (ref "LIGHT@A1") (pin "3") (pinfunction "3_3") (pintype "passive"))
    )
    (net (code "8") (name "A2") (class "Default")
      (node (ref "ATMEGA") (pin "A2") (pinfunction "A2_A2") (pintype "bidirectional"))
      (node (ref "SENSOR@A2") (pin "3") (pinfunction "3_3") (pintype "passive"))
    )
    (net (code "9") (name "A3") (class "Default")
      (node (ref "ATMEGA") (pin "A3") (pinfunction "A3_A3") (pintype "bidirectional"))
      (node (ref "SENSOR@A3") (pin "3") (pinfunction "3_3") (pintype "passive"))
    )
    (net (code "10") (name "A4") (class "Default")
      (node (ref "ATMEGA") (pin "A4") (pinfunction "A4_A4") (pintype "bidirectional"))
      (node (ref "SENSOR@A4") (pin "3") (pinfunction "3_3") (pintype "passive"))
    )
    (net (code "11") (name "A5") (class "Default")
      (node (ref "ATMEGA") (pin "A5") (pinfunction "A5_A5") (pintype "bidirectional"))
      (node (ref "SENSOR@A5") (pin "3") (pinfunction "3_3") (pintype "passive"))
    )
    (net (code "12") (name "A6") (class "Default")
      (node (ref "ANALOG") (pin "1") (pinfunction "1_1") (pintype "passive"))
      (node (ref "ATMEGA") (pin "A6") (pinfunction "A6_A6") (pintype "bidirectional"))
    )
    (net (code "13") (name "A7") (class "Default")
      (node (ref "ANALOG") (pin "2") (pinfunction "2_2") (pintype "passive"))
      (node (ref "ATMEGA") (pin "A7") (pinfunction "A7_A7") (pintype "bidirectional"))
    )
    (net (code "14") (name "A8") (class "Default")
      (node (ref "ANALOG") (pin "3") (pinfunction "3_3") (pintype "passive"))
      (node (ref "ATMEGA") (pin "A8") (pinfunction "A8_A8") (pintype "bidirectional"))
    )
    (net (code "15") (name "A9") (class "Default")
      (node (ref "ANALOG") (pin "4") (pinfunction "4_4") (pintype "passive"))
      (node (ref "ATMEGA") (pin "A9") (pinfunction "A9_A9") (pintype "bidirectional"))
    )
    (net (code "16") (name "A10") (class "Default")
      (node (ref "ANALOG") (pin "5") (pinfunction "5_5") (pintype "passive"))
      (node (ref "ATMEGA") (pin "A10") (pinfunction "A10_A10") (pintype "bidirectional"))
    )
    (net (code "17") (name "A11") (class "Default")
      (node (ref "ANALOG") (pin "6") (pinfunction "6_6") (pintype "passive"))
      (node (ref "ATMEGA") (pin "A11") (pinfunction "A11_A11") (pintype "bidirectional"))
    )
    (net (code "18") (name "A12") (class "Default")
      (node (ref "ANALOG") (pin "7") (pinfunction "7_7") (pintype "passive"))
      (node (ref "ATMEGA") (pin "A12") (pinfunction "A12_A12") (pintype "bidirectional"))
    )
    (net (code "19") (name "A13") (class "Default")
      (node (ref "ANALOG") (pin "8") (pinfunction "8_8") (pintype "passive"))
      (node (ref "ATMEGA") (pin "A13") (pinfunction "A13_A13") (pintype "bidirectional"))
    )
    (net (code "20") (name "A14") (class "Default")
      (node (ref "ANALOG") (pin "9") (pinfunction "9_9") (pintype "passive"))
      (node (ref "ATMEGA") (pin "A14") (pinfunction "A14_A14") (pintype "bidirectional"))
    )
    (net (code "21") (name "A15") (class "Default")
      (node (ref "ANALOG") (pin "10") (pinfunction "10_10") (pintype "passive"))
      (node (ref "ATMEGA") (pin "A15") (pinfunction "A15_A15") (pintype "bidirectional"))
    )
    (net (code "22") (name "D2") (class "Default")
      (node (ref "ATMEGA") (pin "D2") (pinfunction "D2_D2") (pintype "bidirectional"))
      (node (ref "SERVO@D2") (pin "1") (pinfunction "1_1") (pintype "passive"))
    )
    (net (code "23") (name "D3") (class "Default")
      (node (ref "ATMEGA") (pin "D3") (pinfunction "D3_D3") (pintype "bidirectional"))
      (node (ref "SERVO@D3") (pin "1") (pinfunction "1_1") (pintype "passive"))
    )
    (net (code "24") (name "D4") (class "Default")
      (node (ref "ATMEGA") (pin "D4") (pinfunction "D4_D4") (pintype "bidirectional"))
      (node (ref "SERVO@D4") (pin "1") (pinfunction "1_1") (pintype "passive"))
    )
    (net (code "25") (name "D5") (class "Default")
      (node (ref "ATMEGA") (pin "D5") (pinfunction "D5_D5") (pintype "bidirectional"))
      (node (ref "SERVO@D5") (pin "1") (pinfunction "1_1") (pintype "passive"))
    )
    (net (code "26") (name "D6") (class "Default")
      (node (ref "ATMEGA") (pin "D6") (pinfunction "D6_D6") (pintype "bidirectional"))
      (node (ref "SERVO@D6") (pin "1") (pinfunction "1_1") (pintype "passive"))
    )
    (net (code "27") (name "D7") (class "Default")
      (node (ref "ATMEGA") (pin "D7") (pinfunction "D7_D7") (pintype "bidirectional"))
      (node (ref "SERVO@D7") (pin "1") (pinfunction "1_1") (pintype "passive"))
    )
    (net (code "28") (name "D8") (class "Default")
      (node (ref "ATMEGA") (pin "D8") (pinfunction "D8_D8") (pintype "bidirectional"))
      (node (ref "SERVO@D8") (pin "1") (pinfunction "1_1") (pintype "passive"))
    )
    (net (code "29") (name "D9") (class "Default")
      (node (ref "ATMEGA") (pin "D9") (pinfunction "D9_D9") (pintype "bidirectional"))
      (node (ref "SERVO@D9") (pin "1") (pinfunction "1_1") (pintype "passive"))
    )
    (net (code "30") (name "D10") (class "Default")
      (node (ref "ATMEGA") (pin "D10") (pinfunction "D10_D10") (pintype "bidirectional"))
      (node (ref "SERVO@D10") (pin "1") (pinfunction "1_1") (pintype "passive"))
    )
    (net (code "31") (name "D11") (class "Default")
      (node (ref "ATMEGA") (pin "D11") (pinfunction "D11_D11") (pintype "bidirectional"))
      (node (ref "SERVO@D11") (pin "1") (pinfunction "1_1") (pintype "passive"))
    )
    (net (code "32") (name "D12") (class "Default")
      (node (ref "ATMEGA") (pin "D12") (pinfunction "D12_D12") (pintype "bidirectional"))
    )
    (net (code "33") (name "D13") (class "Default")
      (node (ref "ATMEGA") (pin "D13") (pinfunction "D13_D13") (pintype "bidirectional"))
    )
    (net (code "34") (name "D22") (class "Default")
      (node (ref "ATMEGA") (pin "D22") (pinfunction "D22_D22") (pintype "bidirectional"))
      (node (ref "ENV@D22") (pin "3") (pinfunction "3_3") (pintype "passive"))
      (node (ref "SONIC@D22") (pin "3") (pinfunction "3_3") (pintype "passive"))
    )
    (net (code "35") (name "D23") (class "Default")
      (node (ref "ATMEGA") (pin "D23") (pinfunction "D23_D23") (pintype "bidirectional"))
      (node (ref "SONIC@D22") (pin "2") (pinfunction "2_2") (pintype "passive"))
    )
    (net (code "36") (name "D24") (class "Default")
      (node (ref "ATMEGA") (pin "D24") (pinfunction "D24_D24") (pintype "bidirectional"))
      (node (ref "SONIC@D24") (pin "3") (pinfunction "3_3") (pintype "passive"))
    )
    (net (code "37") (name "D25") (class "Default")
      (node (ref "ATMEGA") (pin "D25") (pinfunction "D25_D25") (pintype "bidirectional"))
      (node (ref "SONIC@D24") (pin "2") (pinfunction "2_2") (pintype "passive"))
    )
    (net (code "38") (name "D26") (class "Default")
      (node (ref "ATMEGA") (pin "D26") (pinfunction "D26_D26") (pintype "bidirectional"))
      (node (ref "SONIC@D26") (pin "3") (pinfunction "3_3") (pintype "passive"))
    )
    (net (code "39") (name "D27") (class "Default")
      (node (ref "ATMEGA") (pin "D27") (pinfunction "D27_D27") (pintype "bidirectional"))
      (node (ref "SONIC@D26") (pin "2") (pinfunction "2_2") (pintype "passive"))
    )
    (net (code "40") (name "D28") (class "Default")
      (node (ref "ATMEGA") (pin "D28") (pinfunction "D28_D28") (pintype "bidirectional"))
      (node (ref "SONIC@D28") (pin "3") (pinfunction "3_3") (pintype "passive"))
    )
    (net (code "41") (name "D29") (class "Default")
      (node (ref "ATMEGA") (pin "D29") (pinfunction "D29_D29") (pintype "bidirectional"))
      (node (ref "SONIC@D28") (pin "2") (pinfunction "2_2") (pintype "passive"))
    )
    (net (code "42") (name "D30") (class "Default")
      (node (ref "ATMEGA") (pin "D30") (pinfunction "D30_D30") (pintype "bidirectional"))
      (node (ref "SONIC@D30") (pin "3") (pinfunction "3_3") (pintype "passive"))
    )
    (net (code "43") (name "D31") (class "Default")
      (node (ref "ATMEGA") (pin "D31") (pinfunction "D31_D31") (pintype "bidirectional"))
      (node (ref "SONIC@D30") (pin "2") (pinfunction "2_2") (pintype "passive"))
    )
    (net (code "44") (name "D32") (class "Default")
      (node (ref "ATMEGA") (pin "D32") (pinfunction "D32_D32") (pintype "bidirectional"))
      (node (ref "SONIC@D32") (pin "3") (pinfunction "3_3") (pintype "passive"))
    )
    (net (code "45") (name "D33") (class "Default")
      (node (ref "ATMEGA") (pin "D33") (pinfunction "D33_D33") (pintype "bidirectional"))
      (node (ref "SONIC@D32") (pin "2") (pinfunction "2_2") (pintype "passive"))
    )
    (net (code "46") (name "D34") (class "Default")
      (node (ref "ATMEGA") (pin "D34") (pinfunction "D34_D34") (pintype "bidirectional"))
      (node (ref "SONIC@D34") (pin "3") (pinfunction "3_3") (pintype "passive"))
    )
    (net (code "47") (name "D35") (class "Default")
      (node (ref "ATMEGA") (pin "D35") (pinfunction "D35_D35") (pintype "bidirectional"))
      (node (ref "SONIC@D34") (pin "2") (pinfunction "2_2") (pintype "passive"))
    )
    (net (code "48") (name "D36") (class "Default")
      (node (ref "ATMEGA") (pin "D36") (pinfunction "D36_D36") (pintype "bidirectional"))
      (node (ref "SONIC@D36") (pin "3") (pinfunction "3_3") (pintype "passive"))
    )
    (net (code "49") (name "D37") (class "Default")
      (node (ref "ATMEGA") (pin "D37") (pinfunction "D37_D37") (pintype "bidirectional"))
      (node (ref "SONIC@D36") (pin "2") (pinfunction "2_2") (pintype "passive"))
    )
    (net (code "50") (name "D38") (class "Default")
      (node (ref "ATMEGA") (pin "D38") (pinfunction "D38_D38") (pintype "bidirectional"))
    )
    (net (code "51") (name "D39") (class "Default")
      (node (ref "ATMEGA") (pin "D39") (pinfunction "D39_D39") (pintype "bidirectional"))
      (node (ref "R11") (pin "2") (pinfunction "2_2") (pintype "passive"))
    )
    (net (code "52") (name "D40") (class "Default")
      (node (ref "ATMEGA") (pin "D40") (pinfunction "D40_D40") (pintype "bidirectional"))
      (node (ref "R18") (pin "1") (pinfunction "1_1") (pintype "passive"))
    )
    (net (code "53") (name "D41") (class "Default")
      (node (ref "ATMEGA") (pin "D41") (pinfunction "D41_D41") (pintype "bidirectional"))
      (node (ref "R12") (pin "2") (pinfunction "2_2") (pintype "passive"))
    )
    (net (code "54") (name "D42") (class "Default")
      (node (ref "ATMEGA") (pin "D42") (pinfunction "D42_D42") (pintype "bidirectional"))
      (node (ref "GPS@D40") (pin "2") (pinfunction "2_2") (pintype "passive"))
    )
    (net (code "55") (name "D43") (class "Default")
      (node (ref "ATMEGA") (pin "D43") (pinfunction "D43_D43") (pintype "bidirectional"))
      (node (ref "R13") (pin "2") (pinfunction "2_2") (pintype "passive"))
    )
    (net (code "56") (name "D44") (class "Default")
      (node (ref "ATMEGA") (pin "D44") (pinfunction "D44_D44") (pintype "bidirectional"))
      (node (ref "R16") (pin "1") (pinfunction "1_1") (pintype "passive"))
    )
    (net (code "57") (name "D45") (class "Default")
      (node (ref "ATMEGA") (pin "D45") (pinfunction "D45_D45") (pintype "bidirectional"))
      (node (ref "R14") (pin "2") (pinfunction "2_2") (pintype "passive"))
    )
    (net (code "58") (name "D46") (class "Default")
      (node (ref "ATMEGA") (pin "D46") (pinfunction "D46_D46") (pintype "bidirectional"))
      (node (ref "R17") (pin "1") (pinfunction "1_1") (pintype "passive"))
    )
    (net (code "59") (name "D47") (class "Default")
      (node (ref "ATMEGA") (pin "D47") (pinfunction "D47_D47") (pintype "bidirectional"))
      (node (ref "R15") (pin "2") (pinfunction "2_2") (pintype "passive"))
    )
    (net (code "60") (name "D48") (class "Default")
      (node (ref "ATMEGA") (pin "D48") (pinfunction "D48_D48") (pintype "bidirectional"))
      (node (ref "IR_RECV@D48") (pin "SIG") (pinfunction "SIG_SIG") (pintype "bidirectional"))
      (node (ref "R33") (pin "2") (pinfunction "2_2") (pintype "passive"))
    )
    (net (code "61") (name "D49") (class "Default")
      (node (ref "ATMEGA") (pin "D49") (pinfunction "D49_D49") (pintype "bidirectional"))
      (node (ref "DIGITAL") (pin "1") (pinfunction "1_1") (pintype "passive"))
    )
    (net (code "62") (name "D50") (class "Default")
      (node (ref "ATMEGA") (pin "D50") (pinfunction "D50_D50") (pintype "bidirectional"))
      (node (ref "DIGITAL") (pin "2") (pinfunction "2_2") (pintype "passive"))
    )
    (net (code "63") (name "D51") (class "Default")
      (node (ref "ATMEGA") (pin "D51") (pinfunction "D51_D51") (pintype "bidirectional"))
      (node (ref "DIGITAL") (pin "3") (pinfunction "3_3") (pintype "passive"))
    )
    (net (code "64") (name "D52") (class "Default")
      (node (ref "ATMEGA") (pin "D52") (pinfunction "D52_D52") (pintype "bidirectional"))
      (node (ref "DIGITAL") (pin "4") (pinfunction "4_4") (pintype "passive"))
    )
    (net (code "65") (name "D53") (class "Default")
      (node (ref "ATMEGA") (pin "D53") (pinfunction "D53_D53") (pintype "bidirectional"))
      (node (ref "DIGITAL") (pin "5") (pinfunction "5_5") (pintype "passive"))
    )
    (net (code "66") (name "GND") (class "Default")
      (node (ref "ANALOG") (pin "11") (pinfunction "11_11") (pintype "passive"))
      (node (ref "ATMEGA") (pin "GND0") (pinfunction "GND0_GND0") (pintype "bidirectional"))
      (node (ref "ATMEGA") (pin "GND1") (pinfunction "GND1_GND1") (pintype "bidirectional"))
      (node (ref "ATMEGA") (pin "GND2") (pinfunction "GND2_GND2") (pintype "bidirectional"))
      (node (ref "ATMEGA") (pin "GND3") (pinfunction "GND3_GND3") (pintype "bidirectional"))
      (node (ref "ATMEGA") (pin "GND4") (pinfunction "GND4_GND4") (pintype "bidirectional"))
      (node (ref "AUDIO_IN") (pin "GND") (pinfunction "GND_GND") (pintype "bidirectional"))
      (node (ref "C10") (pin "1") (pinfunction "1_1") (pintype "passive"))
      (node (ref "C11") (pin "1") (pinfunction "1_1") (pintype "passive"))
      (node (ref "C12") (pin "1") (pinfunction "1_1") (pintype "passive"))
      (node (ref "C13") (pin "-") (pinfunction "-_-") (pintype "passive"))
      (node (ref "C14") (pin "-") (pinfunction "-_-") (pintype "passive"))
      (node (ref "C15") (pin "1") (pinfunction "1_1") (pintype "passive"))
      (node (ref "C2") (pin "1") (pinfunction "1_1") (pintype "passive"))
      (node (ref "C21") (pin "1") (pinfunction "1_1") (pintype "passive"))
      (node (ref "C24") (pin "1") (pinfunction "1_1") (pintype "passive"))
      (node (ref "C25") (pin "-") (pinfunction "-_-") (pintype "passive"))
      (node (ref "C26") (pin "1") (pinfunction "1_1") (pintype "passive"))
      (node (ref "C31") (pin "1") (pinfunction "1_1") (pintype "passive"))
      (node (ref "C32") (pin "1") (pinfunction "1_1") (pintype "passive"))
      (node (ref "C33") (pin "1") (pinfunction "1_1") (pintype "passive"))
      (node (ref "C34") (pin "-") (pinfunction "-_-") (pintype "passive"))
      (node (ref "C35") (pin "-") (pinfunction "-_-") (pintype "passive"))
      (node (ref "C36") (pin "1") (pinfunction "1_1") (pintype "passive"))
      (node (ref "C37") (pin "1") (pinfunction "1_1") (pintype "passive"))
      (node (ref "C38") (pin "-") (pinfunction "-_-") (pintype "passive"))
      (node (ref "C5") (pin "1") (pinfunction "1_1") (pintype "passive"))
      (node (ref "C6") (pin "-") (pinfunction "-_-") (pintype "passive"))
      (node (ref "C7") (pin "-") (pinfunction "-_-") (pintype "passive"))
      (node (ref "C8") (pin "1") (pinfunction "1_1") (pintype "passive"))
      (node (ref "C9") (pin "-") (pinfunction "-_-") (pintype "passive"))
      (node (ref "D1") (pin "A") (pinfunction "A_A") (pintype "passive"))
      (node (ref "D2") (pin "A") (pinfunction "A_A") (pintype "passive"))
      (node (ref "D3") (pin "A") (pinfunction "A_A") (pintype "passive"))
      (node (ref "D4") (pin "A") (pinfunction "A_A") (pintype "passive"))
      (node (ref "D7") (pin "A") (pinfunction "A_A") (pintype "passive"))
      (node (ref "D8") (pin "A") (pinfunction "A_A") (pintype "passive"))
      (node (ref "DIGITAL") (pin "6") (pinfunction "6_6") (pintype "passive"))
      (node (ref "ENV@D22") (pin "1") (pinfunction "1_1") (pintype "passive"))
      (node (ref "GPS@D40") (pin "1") (pinfunction "1_1") (pintype "passive"))
      (node (ref "GYROSCOPE@I2C") (pin "GND") (pinfunction "GND_GND") (pintype "bidirectional"))
      (node (ref "I2C") (pin "1") (pinfunction "1_1") (pintype "passive"))
      (node (ref "IC1") (pin "3") (pinfunction "GND_3") (pintype "power_in"))
      (node (ref "IC2") (pin "3") (pinfunction "GND_3") (pintype "power_in"))
      (node (ref "IC2") (pin "5") (pinfunction "~{ON}/OFF_5") (pintype "input"))
      (node (ref "IC3") (pin "3") (pinfunction "GND_3") (pintype "power_in"))
      (node (ref "IC3") (pin "5") (pinfunction "~{ON}/OFF_5") (pintype "input"))
      (node (ref "IC4") (pin "3") (pinfunction "GND_3") (pintype "power_in"))
      (node (ref "IC4") (pin "5") (pinfunction "~{ON}/OFF_5") (pintype "input"))
      (node (ref "IC5") (pin "3") (pinfunction "GND_3") (pintype "power_in"))
      (node (ref "IR_RECV@D48") (pin "GND") (pinfunction "GND_GND") (pintype "bidirectional"))
      (node (ref "LED@D39") (pin "K") (pinfunction "C_K") (pintype "passive"))
      (node (ref "LED@D41") (pin "K") (pinfunction "C_K") (pintype "passive"))
      (node (ref "LED@D43") (pin "K") (pinfunction "C_K") (pintype "passive"))
      (node (ref "LED@D45") (pin "K") (pinfunction "C_K") (pintype "passive"))
      (node (ref "LED@D47") (pin "K") (pinfunction "C_K") (pintype "passive"))
      (node (ref "LIGHT@A1") (pin "1") (pinfunction "1_1") (pintype "passive"))
      (node (ref "POWER") (pin "2") (pinfunction "2_2") (pintype "passive"))
      (node (ref "POWER") (pin "3") (pinfunction "3_3") (pintype "passive"))
      (node (ref "R10") (pin "2") (pinfunction "2_2") (pintype "passive"))
      (node (ref "R21") (pin "2") (pinfunction "2_2") (pintype "passive"))
      (node (ref "R22") (pin "2") (pinfunction "2_2") (pintype "passive"))
      (node (ref "R26") (pin "2") (pinfunction "2_2") (pintype "passive"))
      (node (ref "R29") (pin "2") (pinfunction "2_2") (pintype "passive"))
      (node (ref "R31") (pin "2") (pinfunction "2_2") (pintype "passive"))
      (node (ref "R4") (pin "2") (pinfunction "2_2") (pintype "passive"))
      (node (ref "R8") (pin "2") (pinfunction "2_2") (pintype "passive"))
      (node (ref "SENSOR@A2") (pin "1") (pinfunction "1_1") (pintype "passive"))
      (node (ref "SENSOR@A3") (pin "1") (pinfunction "1_1") (pintype "passive"))
      (node (ref "SENSOR@A4") (pin "1") (pinfunction "1_1") (pintype "passive"))
      (node (ref "SENSOR@A5") (pin "1") (pinfunction "1_1") (pintype "passive"))
      (node (ref "SERIAL") (pin "1") (pinfunction "1_1") (pintype "passive"))
      (node (ref "SERIAL") (pin "5") (pinfunction "5_5") (pintype "passive"))
      (node (ref "SERIAL") (pin "9") (pinfunction "9_9") (pintype "passive"))
      (node (ref "SERVO@D10") (pin "3") (pinfunction "3_3") (pintype "passive"))
      (node (ref "SERVO@D11") (pin "3") (pinfunction "3_3") (pintype "passive"))
      (node (ref "SERVO@D2") (pin "3") (pinfunction "3_3") (pintype "passive"))
      (node (ref "SERVO@D3") (pin "3") (pinfunction "3_3") (pintype "passive"))
      (node (ref "SERVO@D4") (pin "3") (pinfunction "3_3") (pintype "passive"))
      (node (ref "SERVO@D5") (pin "3") (pinfunction "3_3") (pintype "passive"))
      (node (ref "SERVO@D6") (pin "3") (pinfunction "3_3") (pintype "passive"))
      (node (ref "SERVO@D7") (pin "3") (pinfunction "3_3") (pintype "passive"))
      (node (ref "SERVO@D8") (pin "3") (pinfunction "3_3") (pintype "passive"))
      (node (ref "SERVO@D9") (pin "3") (pinfunction "3_3") (pintype "passive"))
      (node (ref "SONIC@D22") (pin "4") (pinfunction "4_4") (pintype "passive"))
      (node (ref "SONIC@D24") (pin "4") (pinfunction "4_4") (pintype "passive"))
      (node (ref "SONIC@D26") (pin "4") (pinfunction "4_4") (pintype "passive"))
      (node (ref "SONIC@D28") (pin "4") (pinfunction "4_4") (pintype "passive"))
      (node (ref "SONIC@D30") (pin "4") (pinfunction "4_4") (pintype "passive"))
      (node (ref "SONIC@D32") (pin "4") (pinfunction "4_4") (pintype "passive"))
      (node (ref "SONIC@D34") (pin "4") (pinfunction "4_4") (pintype "passive"))
      (node (ref "SONIC@D36") (pin "4") (pinfunction "4_4") (pintype "passive"))
      (node (ref "SPEAKER_1") (pin "B") (pinfunction "B_B") (pintype "bidirectional"))
      (node (ref "SPEAKER_2") (pin "B") (pinfunction "B_B") (pintype "bidirectional"))
      (node (ref "T1") (pin "3") (pinfunction "E_3") (pintype "passive"))
      (node (ref "T2") (pin "3") (pinfunction "E_3") (pintype "passive"))
      (node (ref "TR2") (pin "3") (pinfunction "3_3") (pintype "passive"))
      (node (ref "TR4") (pin "3") (pinfunction "3_3") (pintype "passive"))
      (node (ref "U$2") (pin "LA") (pinfunction "L1_LA") (pintype "bidirectional"))
      (node (ref "U$2") (pin "RA") (pinfunction "R1_RA") (pintype "bidirectional"))
      (node (ref "VOUT_1") (pin "B") (pinfunction "B_B") (pintype "bidirectional"))
      (node (ref "VOUT_2") (pin "B") (pinfunction "B_B") (pintype "bidirectional"))
      (node (ref "VOUT_3") (pin "B") (pinfunction "B_B") (pintype "bidirectional"))
    )
    (net (code "67") (name "Net-(AUDIO_IN-PadLEFT)") (class "Default")
      (node (ref "AUDIO_IN") (pin "LEFT") (pinfunction "LEFT_LEFT") (pintype "bidirectional"))
      (node (ref "R1") (pin "1") (pinfunction "1_1") (pintype "passive"))
    )
    (net (code "68") (name "Net-(AUDIO_IN-PadRIGHT)") (class "Default")
      (node (ref "AUDIO_IN") (pin "RIGHT") (pinfunction "RIGHT_RIGHT") (pintype "bidirectional"))
      (node (ref "R23") (pin "1") (pinfunction "1_1") (pintype "passive"))
    )
    (net (code "69") (name "Net-(C3-Pad1)") (class "Default")
      (node (ref "C3") (pin "1") (pinfunction "1_1") (pintype "passive"))
      (node (ref "TR2") (pin "1") (pinfunction "1_1") (pintype "passive"))
    )
    (net (code "70") (name "Net-(C4-Pad2)") (class "Default")
      (node (ref "C4") (pin "2") (pinfunction "2_2") (pintype "passive"))
      (node (ref "R2") (pin "2") (pinfunction "2_2") (pintype "passive"))
    )
    (net (code "71") (name "Net-(C5-Pad2)") (class "Default")
      (node (ref "C5") (pin "2") (pinfunction "2_2") (pintype "passive"))
      (node (ref "R3") (pin "2") (pinfunction "2_2") (pintype "passive"))
      (node (ref "TR2") (pin "2") (pinfunction "2_2") (pintype "passive"))
    )
    (net (code "72") (name "Net-(C16-Pad-)") (class "Default")
      (node (ref "C16") (pin "-") (pinfunction "-_-") (pintype "passive"))
      (node (ref "C17") (pin "2") (pinfunction "2_2") (pintype "passive"))
      (node (ref "SPEAKER_1") (pin "A") (pinfunction "A_A") (pintype "bidirectional"))
    )
    (net (code "73") (name "Net-(C17-Pad1)") (class "Default")
      (node (ref "C17") (pin "1") (pinfunction "1_1") (pintype "passive"))
      (node (ref "R4") (pin "1") (pinfunction "1_1") (pintype "passive"))
    )
    (net (code "74") (name "Net-(C18-Pad1)") (class "Default")
      (node (ref "C18") (pin "1") (pinfunction "1_1") (pintype "passive"))
      (node (ref "R6") (pin "1") (pinfunction "1_1") (pintype "passive"))
    )
    (net (code "75") (name "Net-(C19-Pad-)") (class "Default")
      (node (ref "C19") (pin "-") (pinfunction "-_-") (pintype "passive"))
      (node (ref "R22") (pin "1") (pinfunction "1_1") (pintype "passive"))
      (node (ref "R5") (pin "2") (pinfunction "2_2") (pintype "passive"))
    )
    (net (code "76") (name "Net-(C22-Pad1)") (class "Default")
      (node (ref "C22") (pin "1") (pinfunction "1_1") (pintype "passive"))
      (node (ref "TR4") (pin "1") (pinfunction "1_1") (pintype "passive"))
    )
    (net (code "77") (name "Net-(C23-Pad2)") (class "Default")
      (node (ref "C23") (pin "2") (pinfunction "2_2") (pintype "passive"))
      (node (ref "R24") (pin "2") (pinfunction "2_2") (pintype "passive"))
    )
    (net (code "78") (name "Net-(C24-Pad2)") (class "Default")
      (node (ref "C24") (pin "2") (pinfunction "2_2") (pintype "passive"))
      (node (ref "R25") (pin "2") (pinfunction "2_2") (pintype "passive"))
      (node (ref "TR4") (pin "2") (pinfunction "2_2") (pintype "passive"))
    )
    (net (code "79") (name "Net-(C27-Pad-)") (class "Default")
      (node (ref "C27") (pin "-") (pinfunction "-_-") (pintype "passive"))
      (node (ref "C28") (pin "2") (pinfunction "2_2") (pintype "passive"))
      (node (ref "SPEAKER_2") (pin "A") (pinfunction "A_A") (pintype "bidirectional"))
    )
    (net (code "80") (name "Net-(C28-Pad1)") (class "Default")
      (node (ref "C28") (pin "1") (pinfunction "1_1") (pintype "passive"))
      (node (ref "R26") (pin "1") (pinfunction "1_1") (pintype "passive"))
    )
    (net (code "81") (name "Net-(C29-Pad1)") (class "Default")
      (node (ref "C29") (pin "1") (pinfunction "1_1") (pintype "passive"))
      (node (ref "R28") (pin "1") (pinfunction "1_1") (pintype "passive"))
    )
    (net (code "82") (name "Net-(C30-Pad-)") (class "Default")
      (node (ref "C30") (pin "-") (pinfunction "-_-") (pintype "passive"))
      (node (ref "R27") (pin "2") (pinfunction "2_2") (pintype "passive"))
      (node (ref "R29") (pin "1") (pinfunction "1_1") (pintype "passive"))
    )
    (net (code "83") (name "Net-(C38-Pad+)") (class "Default")
      (node (ref "C38") (pin "+") (pinfunction "+_+") (pintype "passive"))
      (node (ref "IR_RECV@D48") (pin "VCC") (pinfunction "VCC_VCC") (pintype "bidirectional"))
      (node (ref "R32") (pin "2") (pinfunction "2_2") (pintype "passive"))
    )
    (net (code "84") (name "Net-(ENABLE_1-Pad2)") (class "Default")
      (node (ref "ENABLE_1") (pin "2") (pinfunction "2_2") (pintype "passive"))
      (node (ref "POWER_1") (pin "A") (pinfunction "A_A") (pintype "bidirectional"))
    )
    (net (code "85") (name "Net-(ENABLE_2-Pad2)") (class "Default")
      (node (ref "ENABLE_2") (pin "2") (pinfunction "2_2") (pintype "passive"))
      (node (ref "POWER_2") (pin "A") (pinfunction "A_A") (pintype "bidirectional"))
    )
    (net (code "86") (name "Net-(GPS@D40-Pad3)") (class "Default")
      (node (ref "GPS@D40") (pin "3") (pinfunction "3_3") (pintype "passive"))
      (node (ref "R18") (pin "2") (pinfunction "2_2") (pintype "passive"))
      (node (ref "R19") (pin "2") (pinfunction "2_2") (pintype "passive"))
    )
    (net (code "87") (name "Net-(IC1-+IN)") (class "Default")
      (node (ref "C20") (pin "2") (pinfunction "2_2") (pintype "passive"))
      (node (ref "IC1") (pin "1") (pinfunction "+IN_1") (pintype "input"))
    )
    (net (code "88") (name "Net-(IC1--IN)") (class "Default")
      (node (ref "C30") (pin "+") (pinfunction "+_+") (pintype "passive"))
      (node (ref "IC1") (pin "2") (pinfunction "-IN_2") (pintype "input"))
      (node (ref "R28") (pin "2") (pinfunction "2_2") (pintype "passive"))
    )
    (net (code "89") (name "Net-(IC1-OUT)") (class "Default")
      (node (ref "C27") (pin "+") (pinfunction "+_+") (pintype "passive"))
      (node (ref "C29") (pin "2") (pinfunction "2_2") (pintype "passive"))
      (node (ref "IC1") (pin "4") (pinfunction "OUT_4") (pintype "output"))
      (node (ref "R27") (pin "1") (pinfunction "1_1") (pintype "passive"))
    )
    (net (code "90") (name "Net-(IC1-VCC)") (class "Default")
      (node (ref "C25") (pin "+") (pinfunction "+_+") (pintype "passive"))
      (node (ref "C26") (pin "2") (pinfunction "2_2") (pintype "passive"))
      (node (ref "D6") (pin "C") (pinfunction "C_C") (pintype "passive"))
      (node (ref "IC1") (pin "5") (pinfunction "VCC_5") (pintype "power_in"))
    )
    (net (code "91") (name "Net-(IC2-FB)") (class "Default")
      (node (ref "IC2") (pin "4") (pinfunction "FB_4") (pintype "input"))
      (node (ref "R7") (pin "2") (pinfunction "2_2") (pintype "passive"))
      (node (ref "R8") (pin "1") (pinfunction "1_1") (pintype "passive"))
      (node (ref "TR5") (pin "2") (pinfunction "2_2") (pintype "passive"))
    )
    (net (code "92") (name "Net-(IC2-OUT)") (class "Default")
      (node (ref "D2") (pin "C") (pinfunction "C_C") (pintype "passive"))
      (node (ref "IC2") (pin "2") (pinfunction "OUT_2") (pintype "output"))
      (node (ref "L1") (pin "1") (pinfunction "1_1") (pintype "passive"))
    )
    (net (code "93") (name "Net-(IC3-FB)") (class "Default")
      (node (ref "IC3") (pin "4") (pinfunction "FB_4") (pintype "input"))
      (node (ref "R20") (pin "2") (pinfunction "2_2") (pintype "passive"))
      (node (ref "R21") (pin "1") (pinfunction "1_1") (pintype "passive"))
      (node (ref "TR6") (pin "2") (pinfunction "2_2") (pintype "passive"))
    )
    (net (code "94") (name "Net-(IC3-OUT)") (class "Default")
      (node (ref "D4") (pin "C") (pinfunction "C_C") (pintype "passive"))
      (node (ref "IC3") (pin "2") (pinfunction "OUT_2") (pintype "output"))
      (node (ref "L2") (pin "1") (pinfunction "1_1") (pintype "passive"))
    )
    (net (code "95") (name "Net-(IC4-FB)") (class "Default")
      (node (ref "IC4") (pin "4") (pinfunction "FB_4") (pintype "input"))
      (node (ref "R30") (pin "2") (pinfunction "2_2") (pintype "passive"))
      (node (ref "R31") (pin "1") (pinfunction "1_1") (pintype "passive"))
      (node (ref "TR7") (pin "2") (pinfunction "2_2") (pintype "passive"))
    )
    (net (code "96") (name "Net-(IC4-OUT)") (class "Default")
      (node (ref "D8") (pin "C") (pinfunction "C_C") (pintype "passive"))
      (node (ref "IC4") (pin "2") (pinfunction "OUT_2") (pintype "output"))
      (node (ref "L3") (pin "1") (pinfunction "1_1") (pintype "passive"))
    )
    (net (code "97") (name "Net-(IC5-+IN)") (class "Default")
      (node (ref "C1") (pin "2") (pinfunction "2_2") (pintype "passive"))
      (node (ref "IC5") (pin "1") (pinfunction "+IN_1") (pintype "input"))
    )
    (net (code "98") (name "Net-(IC5--IN)") (class "Default")
      (node (ref "C19") (pin "+") (pinfunction "+_+") (pintype "passive"))
      (node (ref "IC5") (pin "2") (pinfunction "-IN_2") (pintype "input"))
      (node (ref "R6") (pin "2") (pinfunction "2_2") (pintype "passive"))
    )
    (net (code "99") (name "Net-(IC5-OUT)") (class "Default")
      (node (ref "C16") (pin "+") (pinfunction "+_+") (pintype "passive"))
      (node (ref "C18") (pin "2") (pinfunction "2_2") (pintype "passive"))
      (node (ref "IC5") (pin "4") (pinfunction "OUT_4") (pintype "output"))
      (node (ref "R5") (pin "1") (pinfunction "1_1") (pintype "passive"))
    )
    (net (code "100") (name "Net-(IC5-VCC)") (class "Default")
      (node (ref "C15") (pin "2") (pinfunction "2_2") (pintype "passive"))
      (node (ref "C6") (pin "+") (pinfunction "+_+") (pintype "passive"))
      (node (ref "D5") (pin "C") (pinfunction "C_C") (pintype "passive"))
      (node (ref "IC5") (pin "5") (pinfunction "VCC_5") (pintype "power_in"))
    )
    (net (code "101") (name "Net-(LED@D39-PadA)") (class "Default")
      (node (ref "LED@D39") (pin "A") (pinfunction "A_A") (pintype "passive"))
      (node (ref "R11") (pin "1") (pinfunction "1_1") (pintype "passive"))
    )
    (net (code "102") (name "Net-(LED@D41-PadA)") (class "Default")
      (node (ref "LED@D41") (pin "A") (pinfunction "A_A") (pintype "passive"))
      (node (ref "R12") (pin "1") (pinfunction "1_1") (pintype "passive"))
    )
    (net (code "103") (name "Net-(LED@D43-PadA)") (class "Default")
      (node (ref "LED@D43") (pin "A") (pinfunction "A_A") (pintype "passive"))
      (node (ref "R13") (pin "1") (pinfunction "1_1") (pintype "passive"))
    )
    (net (code "104") (name "Net-(LED@D45-PadA)") (class "Default")
      (node (ref "LED@D45") (pin "A") (pinfunction "A_A") (pintype "passive"))
      (node (ref "R14") (pin "1") (pinfunction "1_1") (pintype "passive"))
    )
    (net (code "105") (name "Net-(LED@D47-PadA)") (class "Default")
      (node (ref "LED@D47") (pin "A") (pinfunction "A_A") (pintype "passive"))
      (node (ref "R15") (pin "1") (pinfunction "1_1") (pintype "passive"))
    )
    (net (code "106") (name "Net-(MAINSWITCH-Pad2)") (class "Default")
      (node (ref "MAINSWITCH") (pin "2") (pinfunction "2_2") (pintype "passive"))
      (node (ref "POWER") (pin "1") (pinfunction "1_1") (pintype "passive"))
    )
    (net (code "107") (name "Net-(T1-B)") (class "Default")
      (node (ref "R17") (pin "2") (pinfunction "2_2") (pintype "passive"))
      (node (ref "T1") (pin "1") (pinfunction "B_1") (pintype "passive"))
    )
    (net (code "108") (name "Net-(T1-C)") (class "Default")
      (node (ref "POWER_2") (pin "B") (pinfunction "B_B") (pintype "bidirectional"))
      (node (ref "T1") (pin "2") (pinfunction "C_2") (pintype "passive"))
    )
    (net (code "109") (name "Net-(T2-B)") (class "Default")
      (node (ref "R16") (pin "2") (pinfunction "2_2") (pintype "passive"))
      (node (ref "T2") (pin "1") (pinfunction "B_1") (pintype "passive"))
    )
    (net (code "110") (name "Net-(T2-C)") (class "Default")
      (node (ref "POWER_1") (pin "B") (pinfunction "B_B") (pintype "bidirectional"))
      (node (ref "T2") (pin "2") (pinfunction "C_2") (pintype "passive"))
    )
    (net (code "111") (name "Net-(U$2-L2)") (class "Default")
      (node (ref "C22") (pin "2") (pinfunction "2_2") (pintype "passive"))
      (node (ref "R23") (pin "2") (pinfunction "2_2") (pintype "passive"))
      (node (ref "R24") (pin "1") (pinfunction "1_1") (pintype "passive"))
      (node (ref "U$2") (pin "LB") (pinfunction "L2_LB") (pintype "bidirectional"))
    )
    (net (code "112") (name "Net-(U$2-L3)") (class "Default")
      (node (ref "C20") (pin "1") (pinfunction "1_1") (pintype "passive"))
      (node (ref "C21") (pin "2") (pinfunction "2_2") (pintype "passive"))
      (node (ref "C23") (pin "1") (pinfunction "1_1") (pintype "passive"))
      (node (ref "R25") (pin "1") (pinfunction "1_1") (pintype "passive"))
      (node (ref "U$2") (pin "LC") (pinfunction "L3_LC") (pintype "bidirectional"))
    )
    (net (code "113") (name "Net-(U$2-R2)") (class "Default")
      (node (ref "C3") (pin "2") (pinfunction "2_2") (pintype "passive"))
      (node (ref "R1") (pin "2") (pinfunction "2_2") (pintype "passive"))
      (node (ref "R2") (pin "1") (pinfunction "1_1") (pintype "passive"))
      (node (ref "U$2") (pin "RB") (pinfunction "R2_RB") (pintype "bidirectional"))
    )
    (net (code "114") (name "Net-(U$2-R3)") (class "Default")
      (node (ref "C1") (pin "1") (pinfunction "1_1") (pintype "passive"))
      (node (ref "C2") (pin "2") (pinfunction "2_2") (pintype "passive"))
      (node (ref "C4") (pin "1") (pinfunction "1_1") (pintype "passive"))
      (node (ref "R3") (pin "1") (pinfunction "1_1") (pintype "passive"))
      (node (ref "U$2") (pin "RC") (pinfunction "R3_RC") (pintype "bidirectional"))
    )
    (net (code "115") (name "RESET") (class "Default")
      (node (ref "ATMEGA") (pin "RESET") (pinfunction "RESET_RESET") (pintype "bidirectional"))
    )
    (net (code "116") (name "RX1") (class "Default")
      (node (ref "ATMEGA") (pin "RX1") (pinfunction "RX1_RX1") (pintype "bidirectional"))
      (node (ref "SERIAL") (pin "2") (pinfunction "2_2") (pintype "passive"))
    )
    (net (code "117") (name "RX2") (class "Default")
      (node (ref "ATMEGA") (pin "RX2") (pinfunction "RX2_RX2") (pintype "bidirectional"))
      (node (ref "SERIAL") (pin "6") (pinfunction "6_6") (pintype "passive"))
    )
    (net (code "118") (name "RX3") (class "Default")
      (node (ref "ATMEGA") (pin "RX3") (pinfunction "RX3_RX3") (pintype "bidirectional"))
      (node (ref "SERIAL") (pin "10") (pinfunction "10_10") (pintype "passive"))
    )
    (net (code "119") (name "SCL") (class "Default")
      (node (ref "ATMEGA") (pin "SCL1") (pinfunction "SCL1_SCL1") (pintype "bidirectional"))
      (node (ref "GYROSCOPE@I2C") (pin "SCL") (pinfunction "SCL_SCL") (pintype "bidirectional"))
      (node (ref "I2C") (pin "2") (pinfunction "2_2") (pintype "passive"))
    )
    (net (code "120") (name "SDA") (class "Default")
      (node (ref "ATMEGA") (pin "SDA1") (pinfunction "SDA1_SDA1") (pintype "bidirectional"))
      (node (ref "GYROSCOPE@I2C") (pin "SDA") (pinfunction "SDA_SDA") (pintype "bidirectional"))
      (node (ref "I2C") (pin "3") (pinfunction "3_3") (pintype "passive"))
    )
    (net (code "121") (name "TX1") (class "Default")
      (node (ref "ATMEGA") (pin "TX1") (pinfunction "TX1_TX1") (pintype "bidirectional"))
      (node (ref "SERIAL") (pin "3") (pinfunction "3_3") (pintype "passive"))
    )
    (net (code "122") (name "TX2") (class "Default")
      (node (ref "ATMEGA") (pin "TX2") (pinfunction "TX2_TX2") (pintype "bidirectional"))
      (node (ref "SERIAL") (pin "7") (pinfunction "7_7") (pintype "passive"))
    )
    (net (code "123") (name "TX3") (class "Default")
      (node (ref "ATMEGA") (pin "TX3") (pinfunction "TX3_TX3") (pintype "bidirectional"))
      (node (ref "SERIAL") (pin "11") (pinfunction "11_11") (pintype "passive"))
    )
    (net (code "124") (name "VOUT_3A_1") (class "Default")
      (node (ref "C10") (pin "2") (pinfunction "2_2") (pintype "passive"))
      (node (ref "C11") (pin "2") (pinfunction "2_2") (pintype "passive"))
      (node (ref "C9") (pin "+") (pinfunction "+_+") (pintype "passive"))
      (node (ref "ENABLE_1") (pin "1") (pinfunction "1_1") (pintype "passive"))
      (node (ref "L1") (pin "2") (pinfunction "2_2") (pintype "passive"))
      (node (ref "R7") (pin "1") (pinfunction "1_1") (pintype "passive"))
      (node (ref "TR5") (pin "1") (pinfunction "1_1") (pintype "passive"))
      (node (ref "TR5") (pin "3") (pinfunction "3_3") (pintype "passive"))
      (node (ref "VOUT_1") (pin "A") (pinfunction "A_A") (pintype "bidirectional"))
    )
    (net (code "125") (name "VOUT_3A_2") (class "Default")
      (node (ref "C13") (pin "+") (pinfunction "+_+") (pintype "passive"))
      (node (ref "C31") (pin "2") (pinfunction "2_2") (pintype "passive"))
      (node (ref "C32") (pin "2") (pinfunction "2_2") (pintype "passive"))
      (node (ref "ENABLE_2") (pin "1") (pinfunction "1_1") (pintype "passive"))
      (node (ref "L2") (pin "2") (pinfunction "2_2") (pintype "passive"))
      (node (ref "R20") (pin "1") (pinfunction "1_1") (pintype "passive"))
      (node (ref "SERVO@D10") (pin "2") (pinfunction "2_2") (pintype "passive"))
      (node (ref "SERVO@D11") (pin "2") (pinfunction "2_2") (pintype "passive"))
      (node (ref "SERVO@D7") (pin "2") (pinfunction "2_2") (pintype "passive"))
      (node (ref "SERVO@D8") (pin "2") (pinfunction "2_2") (pintype "passive"))
      (node (ref "SERVO@D9") (pin "2") (pinfunction "2_2") (pintype "passive"))
      (node (ref "TR6") (pin "1") (pinfunction "1_1") (pintype "passive"))
      (node (ref "TR6") (pin "3") (pinfunction "3_3") (pintype "passive"))
      (node (ref "VOUT_2") (pin "A") (pinfunction "A_A") (pintype "bidirectional"))
    )
    (net (code "126") (name "VOUT_3A_3") (class "Default")
      (node (ref "C34") (pin "+") (pinfunction "+_+") (pintype "passive"))
      (node (ref "C36") (pin "2") (pinfunction "2_2") (pintype "passive"))
      (node (ref "C37") (pin "2") (pinfunction "2_2") (pintype "passive"))
      (node (ref "L3") (pin "2") (pinfunction "2_2") (pintype "passive"))
      (node (ref "R30") (pin "1") (pinfunction "1_1") (pintype "passive"))
      (node (ref "SERVO@D2") (pin "2") (pinfunction "2_2") (pintype "passive"))
      (node (ref "SERVO@D3") (pin "2") (pinfunction "2_2") (pintype "passive"))
      (node (ref "SERVO@D4") (pin "2") (pinfunction "2_2") (pintype "passive"))
      (node (ref "SERVO@D5") (pin "2") (pinfunction "2_2") (pintype "passive"))
      (node (ref "SERVO@D6") (pin "2") (pinfunction "2_2") (pintype "passive"))
      (node (ref "TR7") (pin "1") (pinfunction "1_1") (pintype "passive"))
      (node (ref "TR7") (pin "3") (pinfunction "3_3") (pintype "passive"))
      (node (ref "VOUT_3") (pin "A") (pinfunction "A_A") (pintype "bidirectional"))
    )
    (net (code "127") (name "unconnected-(ATMEGA-PadAREF)") (class "Default")
      (node (ref "ATMEGA") (pin "AREF") (pinfunction "AREF_AREF") (pintype "bidirectional"))
    )
    (net (code "128") (name "unconnected-(ATMEGA-PadIOREF)") (class "Default")
      (node (ref "ATMEGA") (pin "IOREF") (pinfunction "IOREF_IOREF") (pintype "bidirectional"))
    )
    (net (code "129") (name "unconnected-(ATMEGA-PadN{slash}A)") (class "Default")
      (node (ref "ATMEGA") (pin "N/A") (pinfunction "N/A_N/A") (pintype "bidirectional"))
    )
    (net (code "130") (name "unconnected-(ATMEGA-PadRX0)") (class "Default")
      (node (ref "ATMEGA") (pin "RX0") (pinfunction "RX0_RX0") (pintype "bidirectional"))
    )
    (net (code "131") (name "unconnected-(ATMEGA-PadSCL0)") (class "Default")
      (node (ref "ATMEGA") (pin "SCL0") (pinfunction "SCL0_SCL0") (pintype "bidirectional"))
    )
    (net (code "132") (name "unconnected-(ATMEGA-PadSDA0)") (class "Default")
      (node (ref "ATMEGA") (pin "SDA0") (pinfunction "SDA0_SDA0") (pintype "bidirectional"))
    )
    (net (code "133") (name "unconnected-(ATMEGA-PadTX0)") (class "Default")
      (node (ref "ATMEGA") (pin "TX0") (pinfunction "TX0_TX0") (pintype "bidirectional"))
    )
    (net (code "134") (name "unconnected-(ATMEGA-PadVIN)") (class "Default")
      (node (ref "ATMEGA") (pin "VIN") (pinfunction "VIN_VIN") (pintype "bidirectional"))
    )
    (net (code "135") (name "unconnected-(GYROSCOPE@I2C-PadADO)") (class "Default")
      (node (ref "GYROSCOPE@I2C") (pin "ADO") (pinfunction "ADO_ADO") (pintype "bidirectional"))
    )
    (net (code "136") (name "unconnected-(GYROSCOPE@I2C-PadECL)") (class "Default")
      (node (ref "GYROSCOPE@I2C") (pin "ECL") (pinfunction "ECL_ECL") (pintype "bidirectional"))
    )
    (net (code "137") (name "unconnected-(GYROSCOPE@I2C-PadEDA)") (class "Default")
      (node (ref "GYROSCOPE@I2C") (pin "EDA") (pinfunction "EDA_EDA") (pintype "bidirectional"))
    )
    (net (code "138") (name "unconnected-(GYROSCOPE@I2C-PadFSYNC)") (class "Default")
      (node (ref "GYROSCOPE@I2C") (pin "FSYNC") (pinfunction "FSYNC_FSYNC") (pintype "bidirectional"))
    )
    (net (code "139") (name "unconnected-(GYROSCOPE@I2C-PadINT)") (class "Default")
      (node (ref "GYROSCOPE@I2C") (pin "INT") (pinfunction "INT_INT") (pintype "bidirectional"))
    )
    (net (code "140") (name "unconnected-(GYROSCOPE@I2C-PadNCS)") (class "Default")
      (node (ref "GYROSCOPE@I2C") (pin "NCS") (pinfunction "NCS_NCS") (pintype "bidirectional"))
    )
  )
)
